# AD9959.net
KiCad netlist of a schematic drawn in Altium Designer
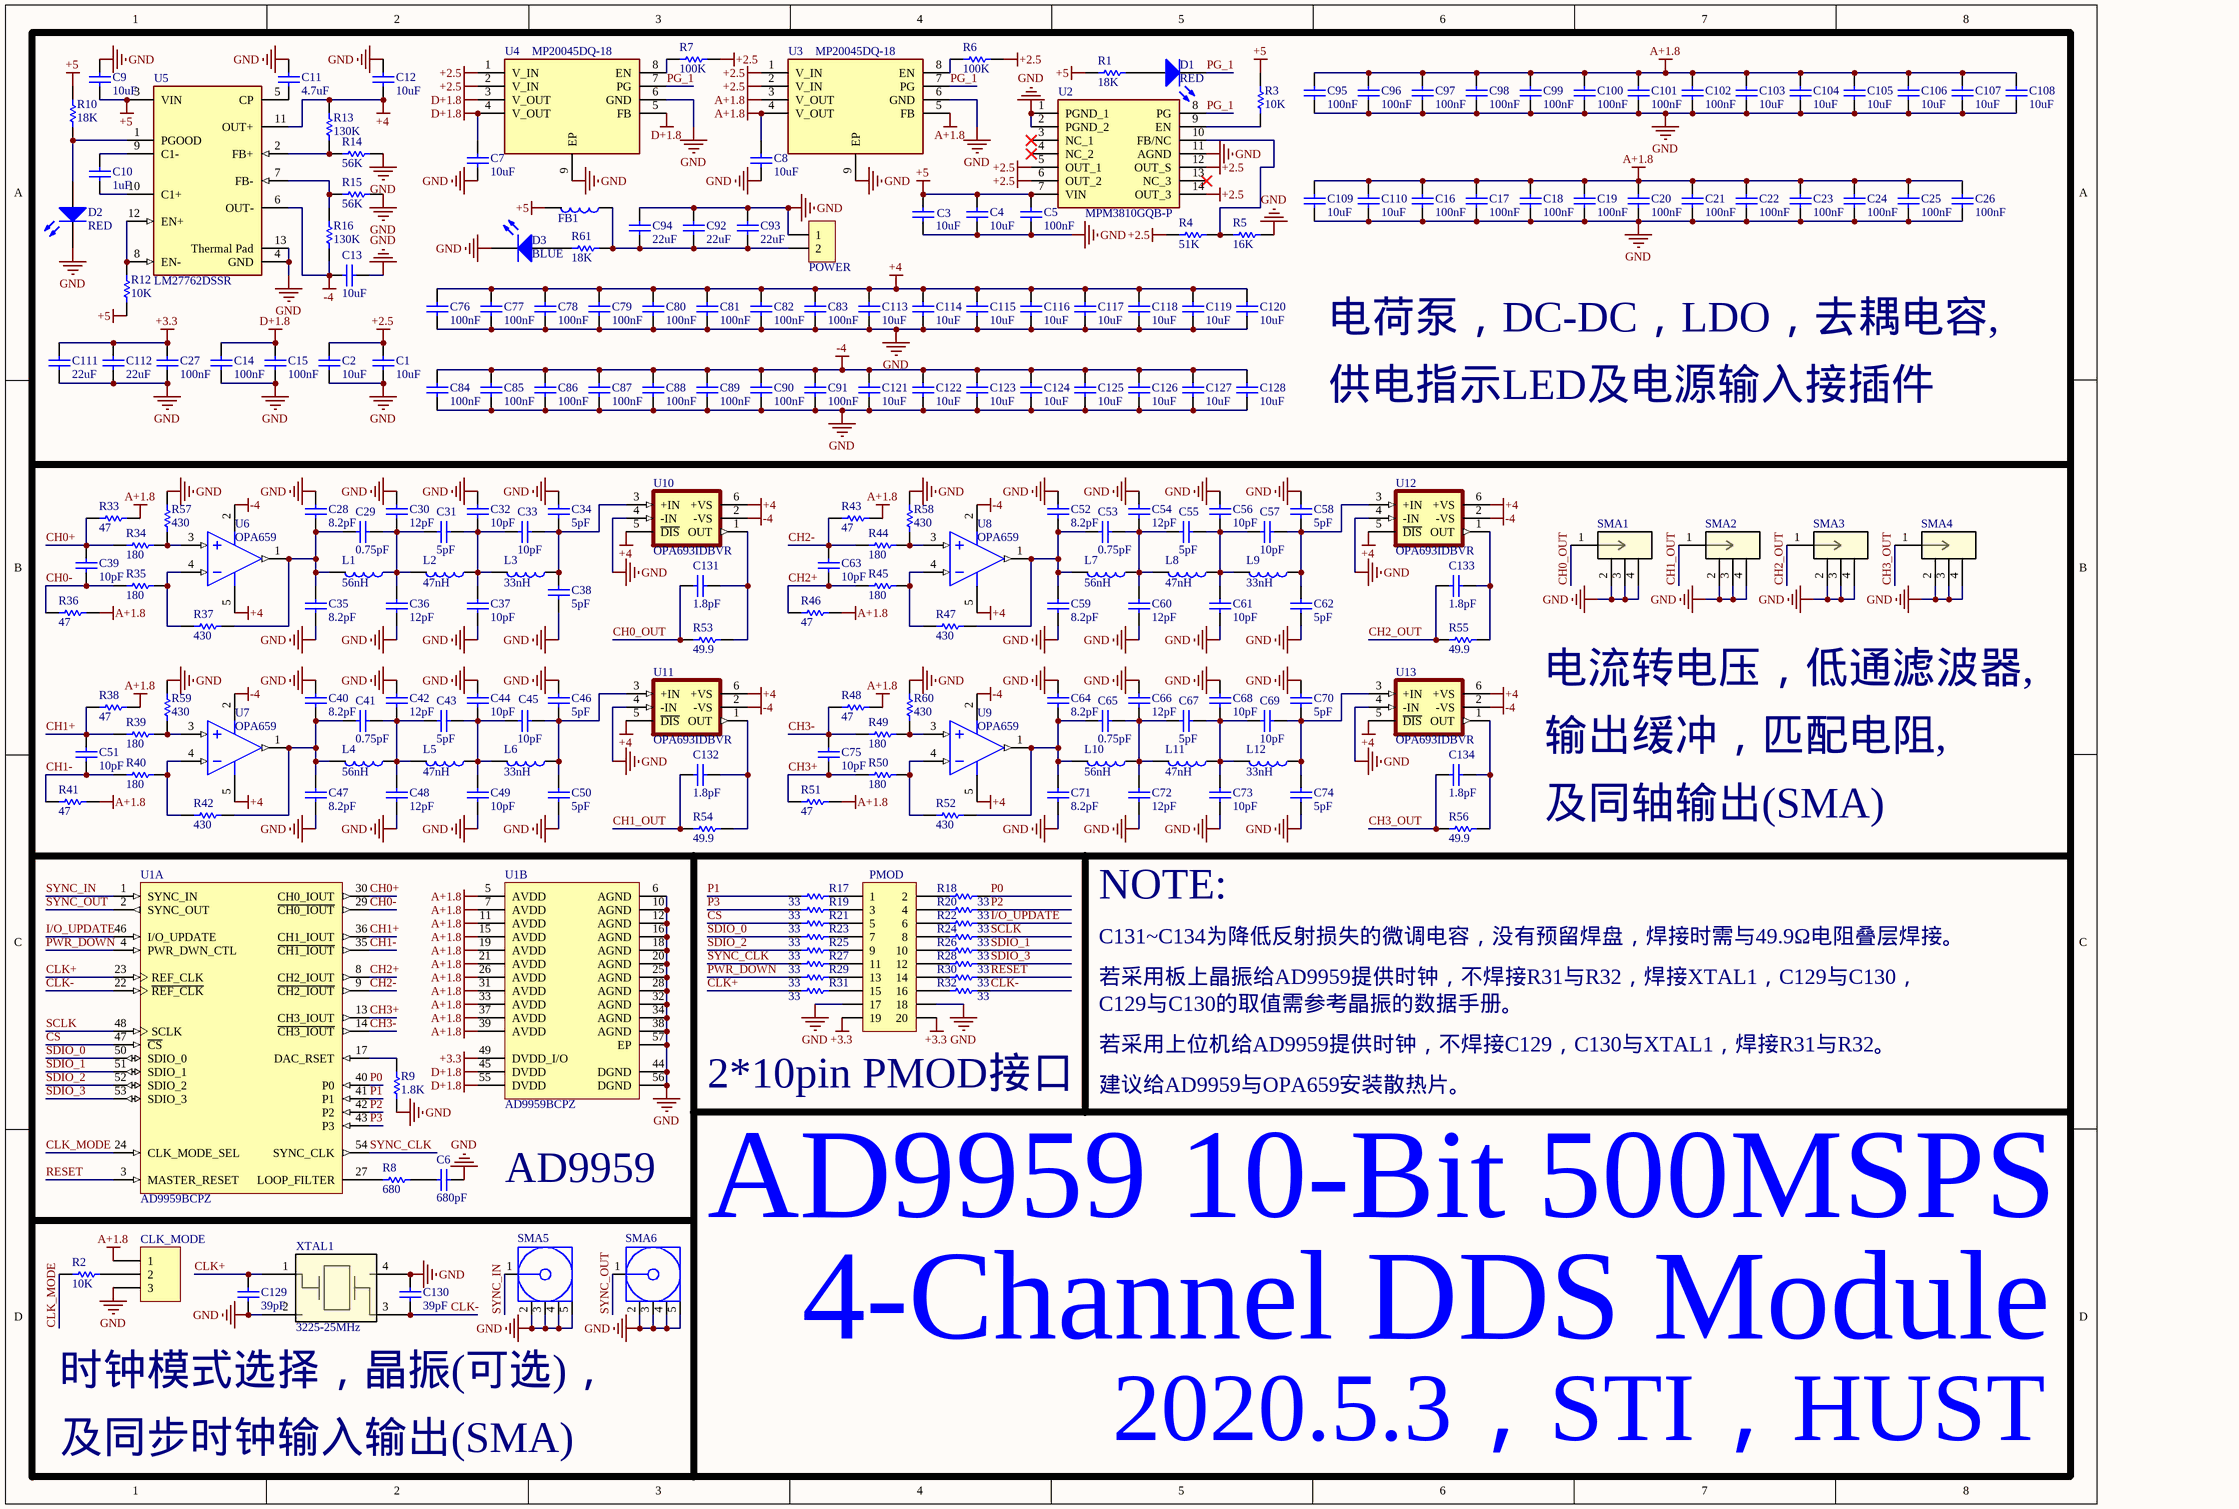
[diagram p0: AD9959.SchDoc]

(export (version "E")
  (design (tool "Eeschema 10.0.6"))
  (components
    (comp (ref "C1")
      (value "10uF")
      (footprint "1608[0603]")
      (description "Capacitor")
      (fields (field (name "PUBLISHER") "Altium Limited"))
      (libsource (lib "My Footprint") (part "CAP"))
    )
    (comp (ref "C2")
      (value "10uF")
      (footprint "1608[0603]")
      (description "Capacitor")
      (fields (field (name "PUBLISHER") "Altium Limited"))
      (libsource (lib "My Footprint") (part "CAP"))
    )
    (comp (ref "C3")
      (value "10uF")
      (footprint "1608[0603]")
      (description "Capacitor")
      (fields (field (name "PUBLISHER") "Altium Limited"))
      (libsource (lib "My Footprint") (part "CAP"))
    )
    (comp (ref "C4")
      (value "10uF")
      (footprint "1608[0603]")
      (description "Capacitor")
      (fields (field (name "PUBLISHER") "Altium Limited"))
      (libsource (lib "My Footprint") (part "CAP"))
    )
    (comp (ref "C5")
      (value "100nF")
      (footprint "0402")
      (description "Capacitor")
      (fields (field (name "PUBLISHER") "Altium Limited"))
      (libsource (lib "My Footprint") (part "CAP"))
    )
    (comp (ref "C6")
      (value "680pF")
      (footprint "0402")
      (description "Capacitor")
      (fields (field (name "PUBLISHER") "Altium Limited"))
      (libsource (lib "My Footprint") (part "CAP"))
    )
    (comp (ref "C7")
      (value "10uF")
      (footprint "1608[0603]")
      (description "Capacitor")
      (fields (field (name "PUBLISHER") "Altium Limited"))
      (libsource (lib "My Footprint") (part "CAP"))
    )
    (comp (ref "C8")
      (value "10uF")
      (footprint "1608[0603]")
      (description "Capacitor")
      (fields (field (name "PUBLISHER") "Altium Limited"))
      (libsource (lib "My Footprint") (part "CAP"))
    )
    (comp (ref "C9")
      (value "10uF")
      (footprint "1608[0603]")
      (description "Capacitor")
      (fields (field (name "PUBLISHER") "Altium Limited"))
      (libsource (lib "My Footprint") (part "CAP"))
    )
    (comp (ref "C10")
      (value "1uF")
      (footprint "0402")
      (description "Capacitor")
      (fields (field (name "PUBLISHER") "Altium Limited"))
      (libsource (lib "My Footprint") (part "CAP"))
    )
    (comp (ref "C11")
      (value "4.7uF")
      (footprint "1608[0603]")
      (description "Capacitor")
      (fields (field (name "PUBLISHER") "Altium Limited"))
      (libsource (lib "My Footprint") (part "CAP"))
    )
    (comp (ref "C12")
      (value "10uF")
      (footprint "1608[0603]")
      (description "Capacitor")
      (fields (field (name "PUBLISHER") "Altium Limited"))
      (libsource (lib "My Footprint") (part "CAP"))
    )
    (comp (ref "C13")
      (value "10uF")
      (footprint "1608[0603]")
      (description "Capacitor")
      (fields (field (name "PUBLISHER") "Altium Limited"))
      (libsource (lib "My Footprint") (part "CAP"))
    )
    (comp (ref "C14")
      (value "100nF")
      (footprint "0402")
      (description "Capacitor")
      (fields (field (name "PUBLISHER") "Altium Limited"))
      (libsource (lib "My Footprint") (part "CAP"))
    )
    (comp (ref "C15")
      (value "100nF")
      (footprint "0402")
      (description "Capacitor")
      (fields (field (name "PUBLISHER") "Altium Limited"))
      (libsource (lib "My Footprint") (part "CAP"))
    )
    (comp (ref "C16")
      (value "100nF")
      (footprint "0402")
      (description "Capacitor")
      (fields (field (name "PUBLISHER") "Altium Limited"))
      (libsource (lib "My Footprint") (part "CAP"))
    )
    (comp (ref "C17")
      (value "100nF")
      (footprint "0402")
      (description "Capacitor")
      (fields (field (name "PUBLISHER") "Altium Limited"))
      (libsource (lib "My Footprint") (part "CAP"))
    )
    (comp (ref "C18")
      (value "100nF")
      (footprint "0402")
      (description "Capacitor")
      (fields (field (name "PUBLISHER") "Altium Limited"))
      (libsource (lib "My Footprint") (part "CAP"))
    )
    (comp (ref "C19")
      (value "100nF")
      (footprint "0402")
      (description "Capacitor")
      (fields (field (name "PUBLISHER") "Altium Limited"))
      (libsource (lib "My Footprint") (part "CAP"))
    )
    (comp (ref "C20")
      (value "100nF")
      (footprint "0402")
      (description "Capacitor")
      (fields (field (name "PUBLISHER") "Altium Limited"))
      (libsource (lib "My Footprint") (part "CAP"))
    )
    (comp (ref "C21")
      (value "100nF")
      (footprint "0402")
      (description "Capacitor")
      (fields (field (name "PUBLISHER") "Altium Limited"))
      (libsource (lib "My Footprint") (part "CAP"))
    )
    (comp (ref "C22")
      (value "100nF")
      (footprint "0402")
      (description "Capacitor")
      (fields (field (name "PUBLISHER") "Altium Limited"))
      (libsource (lib "My Footprint") (part "CAP"))
    )
    (comp (ref "C23")
      (value "100nF")
      (footprint "0402")
      (description "Capacitor")
      (fields (field (name "PUBLISHER") "Altium Limited"))
      (libsource (lib "My Footprint") (part "CAP"))
    )
    (comp (ref "C24")
      (value "100nF")
      (footprint "0402")
      (description "Capacitor")
      (fields (field (name "PUBLISHER") "Altium Limited"))
      (libsource (lib "My Footprint") (part "CAP"))
    )
    (comp (ref "C25")
      (value "100nF")
      (footprint "0402")
      (description "Capacitor")
      (fields (field (name "PUBLISHER") "Altium Limited"))
      (libsource (lib "My Footprint") (part "CAP"))
    )
    (comp (ref "C26")
      (value "100nF")
      (footprint "0402")
      (description "Capacitor")
      (fields (field (name "PUBLISHER") "Altium Limited"))
      (libsource (lib "My Footprint") (part "CAP"))
    )
    (comp (ref "C27")
      (value "100nF")
      (footprint "0402")
      (description "Capacitor")
      (fields (field (name "PUBLISHER") "Altium Limited"))
      (libsource (lib "My Footprint") (part "CAP"))
    )
    (comp (ref "C28")
      (value "8.2pF")
      (footprint "0402")
      (description "Capacitor")
      (fields (field (name "PUBLISHER") "Altium Limited"))
      (libsource (lib "My Footprint") (part "CAP"))
    )
    (comp (ref "C29")
      (value "0.75pF")
      (footprint "0402")
      (description "Capacitor")
      (fields (field (name "PUBLISHER") "Altium Limited"))
      (libsource (lib "My Footprint") (part "CAP"))
    )
    (comp (ref "C30")
      (value "12pF")
      (footprint "0402")
      (description "Capacitor")
      (fields (field (name "PUBLISHER") "Altium Limited"))
      (libsource (lib "My Footprint") (part "CAP"))
    )
    (comp (ref "C31")
      (value "5pF")
      (footprint "0402")
      (description "Capacitor")
      (fields (field (name "PUBLISHER") "Altium Limited"))
      (libsource (lib "My Footprint") (part "CAP"))
    )
    (comp (ref "C32")
      (value "10pF")
      (footprint "0402")
      (description "Capacitor")
      (fields (field (name "PUBLISHER") "Altium Limited"))
      (libsource (lib "My Footprint") (part "CAP"))
    )
    (comp (ref "C33")
      (value "10pF")
      (footprint "0402")
      (description "Capacitor")
      (fields (field (name "PUBLISHER") "Altium Limited"))
      (libsource (lib "My Footprint") (part "CAP"))
    )
    (comp (ref "C34")
      (value "5pF")
      (footprint "0402")
      (description "Capacitor")
      (fields (field (name "PUBLISHER") "Altium Limited"))
      (libsource (lib "My Footprint") (part "CAP"))
    )
    (comp (ref "C35")
      (value "8.2pF")
      (footprint "0402")
      (description "Capacitor")
      (fields (field (name "PUBLISHER") "Altium Limited"))
      (libsource (lib "My Footprint") (part "CAP"))
    )
    (comp (ref "C36")
      (value "12pF")
      (footprint "0402")
      (description "Capacitor")
      (fields (field (name "PUBLISHER") "Altium Limited"))
      (libsource (lib "My Footprint") (part "CAP"))
    )
    (comp (ref "C37")
      (value "10pF")
      (footprint "0402")
      (description "Capacitor")
      (fields (field (name "PUBLISHER") "Altium Limited"))
      (libsource (lib "My Footprint") (part "CAP"))
    )
    (comp (ref "C38")
      (value "5pF")
      (footprint "0402")
      (description "Capacitor")
      (fields (field (name "PUBLISHER") "Altium Limited"))
      (libsource (lib "My Footprint") (part "CAP"))
    )
    (comp (ref "C39")
      (value "10pF")
      (footprint "0402")
      (description "Capacitor")
      (fields (field (name "PUBLISHER") "Altium Limited"))
      (libsource (lib "My Footprint") (part "CAP"))
    )
    (comp (ref "C40")
      (value "8.2pF")
      (footprint "0402")
      (description "Capacitor")
      (fields (field (name "PUBLISHER") "Altium Limited"))
      (libsource (lib "My Footprint") (part "CAP"))
    )
    (comp (ref "C41")
      (value "0.75pF")
      (footprint "0402")
      (description "Capacitor")
      (fields (field (name "PUBLISHER") "Altium Limited"))
      (libsource (lib "My Footprint") (part "CAP"))
    )
    (comp (ref "C42")
      (value "12pF")
      (footprint "0402")
      (description "Capacitor")
      (fields (field (name "PUBLISHER") "Altium Limited"))
      (libsource (lib "My Footprint") (part "CAP"))
    )
    (comp (ref "C43")
      (value "5pF")
      (footprint "0402")
      (description "Capacitor")
      (fields (field (name "PUBLISHER") "Altium Limited"))
      (libsource (lib "My Footprint") (part "CAP"))
    )
    (comp (ref "C44")
      (value "10pF")
      (footprint "0402")
      (description "Capacitor")
      (fields (field (name "PUBLISHER") "Altium Limited"))
      (libsource (lib "My Footprint") (part "CAP"))
    )
    (comp (ref "C45")
      (value "10pF")
      (footprint "0402")
      (description "Capacitor")
      (fields (field (name "PUBLISHER") "Altium Limited"))
      (libsource (lib "My Footprint") (part "CAP"))
    )
    (comp (ref "C46")
      (value "5pF")
      (footprint "0402")
      (description "Capacitor")
      (fields (field (name "PUBLISHER") "Altium Limited"))
      (libsource (lib "My Footprint") (part "CAP"))
    )
    (comp (ref "C47")
      (value "8.2pF")
      (footprint "0402")
      (description "Capacitor")
      (fields (field (name "PUBLISHER") "Altium Limited"))
      (libsource (lib "My Footprint") (part "CAP"))
    )
    (comp (ref "C48")
      (value "12pF")
      (footprint "0402")
      (description "Capacitor")
      (fields (field (name "PUBLISHER") "Altium Limited"))
      (libsource (lib "My Footprint") (part "CAP"))
    )
    (comp (ref "C49")
      (value "10pF")
      (footprint "0402")
      (description "Capacitor")
      (fields (field (name "PUBLISHER") "Altium Limited"))
      (libsource (lib "My Footprint") (part "CAP"))
    )
    (comp (ref "C50")
      (value "5pF")
      (footprint "0402")
      (description "Capacitor")
      (fields (field (name "PUBLISHER") "Altium Limited"))
      (libsource (lib "My Footprint") (part "CAP"))
    )
    (comp (ref "C51")
      (value "10pF")
      (footprint "0402")
      (description "Capacitor")
      (fields (field (name "PUBLISHER") "Altium Limited"))
      (libsource (lib "My Footprint") (part "CAP"))
    )
    (comp (ref "C52")
      (value "8.2pF")
      (footprint "0402")
      (description "Capacitor")
      (fields (field (name "PUBLISHER") "Altium Limited"))
      (libsource (lib "My Footprint") (part "CAP"))
    )
    (comp (ref "C53")
      (value "0.75pF")
      (footprint "0402")
      (description "Capacitor")
      (fields (field (name "PUBLISHER") "Altium Limited"))
      (libsource (lib "My Footprint") (part "CAP"))
    )
    (comp (ref "C54")
      (value "12pF")
      (footprint "0402")
      (description "Capacitor")
      (fields (field (name "PUBLISHER") "Altium Limited"))
      (libsource (lib "My Footprint") (part "CAP"))
    )
    (comp (ref "C55")
      (value "5pF")
      (footprint "0402")
      (description "Capacitor")
      (fields (field (name "PUBLISHER") "Altium Limited"))
      (libsource (lib "My Footprint") (part "CAP"))
    )
    (comp (ref "C56")
      (value "10pF")
      (footprint "0402")
      (description "Capacitor")
      (fields (field (name "PUBLISHER") "Altium Limited"))
      (libsource (lib "My Footprint") (part "CAP"))
    )
    (comp (ref "C57")
      (value "10pF")
      (footprint "0402")
      (description "Capacitor")
      (fields (field (name "PUBLISHER") "Altium Limited"))
      (libsource (lib "My Footprint") (part "CAP"))
    )
    (comp (ref "C58")
      (value "5pF")
      (footprint "0402")
      (description "Capacitor")
      (fields (field (name "PUBLISHER") "Altium Limited"))
      (libsource (lib "My Footprint") (part "CAP"))
    )
    (comp (ref "C59")
      (value "8.2pF")
      (footprint "0402")
      (description "Capacitor")
      (fields (field (name "PUBLISHER") "Altium Limited"))
      (libsource (lib "My Footprint") (part "CAP"))
    )
    (comp (ref "C60")
      (value "12pF")
      (footprint "0402")
      (description "Capacitor")
      (fields (field (name "PUBLISHER") "Altium Limited"))
      (libsource (lib "My Footprint") (part "CAP"))
    )
    (comp (ref "C61")
      (value "10pF")
      (footprint "0402")
      (description "Capacitor")
      (fields (field (name "PUBLISHER") "Altium Limited"))
      (libsource (lib "My Footprint") (part "CAP"))
    )
    (comp (ref "C62")
      (value "5pF")
      (footprint "0402")
      (description "Capacitor")
      (fields (field (name "PUBLISHER") "Altium Limited"))
      (libsource (lib "My Footprint") (part "CAP"))
    )
    (comp (ref "C63")
      (value "10pF")
      (footprint "0402")
      (description "Capacitor")
      (fields (field (name "PUBLISHER") "Altium Limited"))
      (libsource (lib "My Footprint") (part "CAP"))
    )
    (comp (ref "C64")
      (value "8.2pF")
      (footprint "0402")
      (description "Capacitor")
      (fields (field (name "PUBLISHER") "Altium Limited"))
      (libsource (lib "My Footprint") (part "CAP"))
    )
    (comp (ref "C65")
      (value "0.75pF")
      (footprint "0402")
      (description "Capacitor")
      (fields (field (name "PUBLISHER") "Altium Limited"))
      (libsource (lib "My Footprint") (part "CAP"))
    )
    (comp (ref "C66")
      (value "12pF")
      (footprint "0402")
      (description "Capacitor")
      (fields (field (name "PUBLISHER") "Altium Limited"))
      (libsource (lib "My Footprint") (part "CAP"))
    )
    (comp (ref "C67")
      (value "5pF")
      (footprint "0402")
      (description "Capacitor")
      (fields (field (name "PUBLISHER") "Altium Limited"))
      (libsource (lib "My Footprint") (part "CAP"))
    )
    (comp (ref "C68")
      (value "10pF")
      (footprint "0402")
      (description "Capacitor")
      (fields (field (name "PUBLISHER") "Altium Limited"))
      (libsource (lib "My Footprint") (part "CAP"))
    )
    (comp (ref "C69")
      (value "10pF")
      (footprint "0402")
      (description "Capacitor")
      (fields (field (name "PUBLISHER") "Altium Limited"))
      (libsource (lib "My Footprint") (part "CAP"))
    )
    (comp (ref "C70")
      (value "5pF")
      (footprint "0402")
      (description "Capacitor")
      (fields (field (name "PUBLISHER") "Altium Limited"))
      (libsource (lib "My Footprint") (part "CAP"))
    )
    (comp (ref "C71")
      (value "8.2pF")
      (footprint "0402")
      (description "Capacitor")
      (fields (field (name "PUBLISHER") "Altium Limited"))
      (libsource (lib "My Footprint") (part "CAP"))
    )
    (comp (ref "C72")
      (value "12pF")
      (footprint "0402")
      (description "Capacitor")
      (fields (field (name "PUBLISHER") "Altium Limited"))
      (libsource (lib "My Footprint") (part "CAP"))
    )
    (comp (ref "C73")
      (value "10pF")
      (footprint "0402")
      (description "Capacitor")
      (fields (field (name "PUBLISHER") "Altium Limited"))
      (libsource (lib "My Footprint") (part "CAP"))
    )
    (comp (ref "C74")
      (value "5pF")
      (footprint "0402")
      (description "Capacitor")
      (fields (field (name "PUBLISHER") "Altium Limited"))
      (libsource (lib "My Footprint") (part "CAP"))
    )
    (comp (ref "C75")
      (value "10pF")
      (footprint "0402")
      (description "Capacitor")
      (fields (field (name "PUBLISHER") "Altium Limited"))
      (libsource (lib "My Footprint") (part "CAP"))
    )
    (comp (ref "C76")
      (value "100nF")
      (footprint "0402")
      (description "Capacitor")
      (fields (field (name "PUBLISHER") "Altium Limited"))
      (libsource (lib "My Footprint") (part "CAP"))
    )
    (comp (ref "C77")
      (value "100nF")
      (footprint "0402")
      (description "Capacitor")
      (fields (field (name "PUBLISHER") "Altium Limited"))
      (libsource (lib "My Footprint") (part "CAP"))
    )
    (comp (ref "C78")
      (value "100nF")
      (footprint "0402")
      (description "Capacitor")
      (fields (field (name "PUBLISHER") "Altium Limited"))
      (libsource (lib "My Footprint") (part "CAP"))
    )
    (comp (ref "C79")
      (value "100nF")
      (footprint "0402")
      (description "Capacitor")
      (fields (field (name "PUBLISHER") "Altium Limited"))
      (libsource (lib "My Footprint") (part "CAP"))
    )
    (comp (ref "C80")
      (value "100nF")
      (footprint "0402")
      (description "Capacitor")
      (fields (field (name "PUBLISHER") "Altium Limited"))
      (libsource (lib "My Footprint") (part "CAP"))
    )
    (comp (ref "C81")
      (value "100nF")
      (footprint "0402")
      (description "Capacitor")
      (fields (field (name "PUBLISHER") "Altium Limited"))
      (libsource (lib "My Footprint") (part "CAP"))
    )
    (comp (ref "C82")
      (value "100nF")
      (footprint "0402")
      (description "Capacitor")
      (fields (field (name "PUBLISHER") "Altium Limited"))
      (libsource (lib "My Footprint") (part "CAP"))
    )
    (comp (ref "C83")
      (value "100nF")
      (footprint "0402")
      (description "Capacitor")
      (fields (field (name "PUBLISHER") "Altium Limited"))
      (libsource (lib "My Footprint") (part "CAP"))
    )
    (comp (ref "C84")
      (value "100nF")
      (footprint "0402")
      (description "Capacitor")
      (fields (field (name "PUBLISHER") "Altium Limited"))
      (libsource (lib "My Footprint") (part "CAP"))
    )
    (comp (ref "C85")
      (value "100nF")
      (footprint "0402")
      (description "Capacitor")
      (fields (field (name "PUBLISHER") "Altium Limited"))
      (libsource (lib "My Footprint") (part "CAP"))
    )
    (comp (ref "C86")
      (value "100nF")
      (footprint "0402")
      (description "Capacitor")
      (fields (field (name "PUBLISHER") "Altium Limited"))
      (libsource (lib "My Footprint") (part "CAP"))
    )
    (comp (ref "C87")
      (value "100nF")
      (footprint "0402")
      (description "Capacitor")
      (fields (field (name "PUBLISHER") "Altium Limited"))
      (libsource (lib "My Footprint") (part "CAP"))
    )
    (comp (ref "C88")
      (value "100nF")
      (footprint "0402")
      (description "Capacitor")
      (fields (field (name "PUBLISHER") "Altium Limited"))
      (libsource (lib "My Footprint") (part "CAP"))
    )
    (comp (ref "C89")
      (value "100nF")
      (footprint "0402")
      (description "Capacitor")
      (fields (field (name "PUBLISHER") "Altium Limited"))
      (libsource (lib "My Footprint") (part "CAP"))
    )
    (comp (ref "C90")
      (value "100nF")
      (footprint "0402")
      (description "Capacitor")
      (fields (field (name "PUBLISHER") "Altium Limited"))
      (libsource (lib "My Footprint") (part "CAP"))
    )
    (comp (ref "C91")
      (value "100nF")
      (footprint "0402")
      (description "Capacitor")
      (fields (field (name "PUBLISHER") "Altium Limited"))
      (libsource (lib "My Footprint") (part "CAP"))
    )
    (comp (ref "C92")
      (value "22uF")
      (footprint "6-0805_L")
      (description "Capacitor")
      (fields (field (name "PUBLISHER") "Altium Limited"))
      (libsource (lib "My Footprint") (part "CAP"))
    )
    (comp (ref "C93")
      (value "22uF")
      (footprint "6-0805_L")
      (description "Capacitor")
      (fields (field (name "PUBLISHER") "Altium Limited"))
      (libsource (lib "My Footprint") (part "CAP"))
    )
    (comp (ref "C94")
      (value "22uF")
      (footprint "6-0805_L")
      (description "Capacitor")
      (fields (field (name "PUBLISHER") "Altium Limited"))
      (libsource (lib "My Footprint") (part "CAP"))
    )
    (comp (ref "C95")
      (value "100nF")
      (footprint "0402")
      (description "Capacitor")
      (fields (field (name "PUBLISHER") "Altium Limited"))
      (libsource (lib "My Footprint") (part "CAP"))
    )
    (comp (ref "C96")
      (value "100nF")
      (footprint "0402")
      (description "Capacitor")
      (fields (field (name "PUBLISHER") "Altium Limited"))
      (libsource (lib "My Footprint") (part "CAP"))
    )
    (comp (ref "C97")
      (value "100nF")
      (footprint "0402")
      (description "Capacitor")
      (fields (field (name "PUBLISHER") "Altium Limited"))
      (libsource (lib "My Footprint") (part "CAP"))
    )
    (comp (ref "C98")
      (value "100nF")
      (footprint "0402")
      (description "Capacitor")
      (fields (field (name "PUBLISHER") "Altium Limited"))
      (libsource (lib "My Footprint") (part "CAP"))
    )
    (comp (ref "C99")
      (value "100nF")
      (footprint "0402")
      (description "Capacitor")
      (fields (field (name "PUBLISHER") "Altium Limited"))
      (libsource (lib "My Footprint") (part "CAP"))
    )
    (comp (ref "C100")
      (value "100nF")
      (footprint "0402")
      (description "Capacitor")
      (fields (field (name "PUBLISHER") "Altium Limited"))
      (libsource (lib "My Footprint") (part "CAP"))
    )
    (comp (ref "C101")
      (value "100nF")
      (footprint "0402")
      (description "Capacitor")
      (fields (field (name "PUBLISHER") "Altium Limited"))
      (libsource (lib "My Footprint") (part "CAP"))
    )
    (comp (ref "C102")
      (value "100nF")
      (footprint "0402")
      (description "Capacitor")
      (fields (field (name "PUBLISHER") "Altium Limited"))
      (libsource (lib "My Footprint") (part "CAP"))
    )
    (comp (ref "C103")
      (value "10uF")
      (footprint "0402")
      (description "Capacitor")
      (fields (field (name "PUBLISHER") "Altium Limited"))
      (libsource (lib "My Footprint") (part "CAP"))
    )
    (comp (ref "C104")
      (value "10uF")
      (footprint "0402")
      (description "Capacitor")
      (fields (field (name "PUBLISHER") "Altium Limited"))
      (libsource (lib "My Footprint") (part "CAP"))
    )
    (comp (ref "C105")
      (value "10uF")
      (footprint "0402")
      (description "Capacitor")
      (fields (field (name "PUBLISHER") "Altium Limited"))
      (libsource (lib "My Footprint") (part "CAP"))
    )
    (comp (ref "C106")
      (value "10uF")
      (footprint "0402")
      (description "Capacitor")
      (fields (field (name "PUBLISHER") "Altium Limited"))
      (libsource (lib "My Footprint") (part "CAP"))
    )
    (comp (ref "C107")
      (value "10uF")
      (footprint "0402")
      (description "Capacitor")
      (fields (field (name "PUBLISHER") "Altium Limited"))
      (libsource (lib "My Footprint") (part "CAP"))
    )
    (comp (ref "C108")
      (value "10uF")
      (footprint "0402")
      (description "Capacitor")
      (fields (field (name "PUBLISHER") "Altium Limited"))
      (libsource (lib "My Footprint") (part "CAP"))
    )
    (comp (ref "C109")
      (value "10uF")
      (footprint "0402")
      (description "Capacitor")
      (fields (field (name "PUBLISHER") "Altium Limited"))
      (libsource (lib "My Footprint") (part "CAP"))
    )
    (comp (ref "C110")
      (value "10uF")
      (footprint "0402")
      (description "Capacitor")
      (fields (field (name "PUBLISHER") "Altium Limited"))
      (libsource (lib "My Footprint") (part "CAP"))
    )
    (comp (ref "C111")
      (value "22uF")
      (footprint "6-0805_L")
      (description "Capacitor")
      (fields (field (name "PUBLISHER") "Altium Limited"))
      (libsource (lib "My Footprint") (part "CAP"))
    )
    (comp (ref "C112")
      (value "22uF")
      (footprint "6-0805_L")
      (description "Capacitor")
      (fields (field (name "PUBLISHER") "Altium Limited"))
      (libsource (lib "My Footprint") (part "CAP"))
    )
    (comp (ref "C113")
      (value "10uF")
      (footprint "0402")
      (description "Capacitor")
      (fields (field (name "PUBLISHER") "Altium Limited"))
      (libsource (lib "My Footprint") (part "CAP"))
    )
    (comp (ref "C114")
      (value "10uF")
      (footprint "0402")
      (description "Capacitor")
      (fields (field (name "PUBLISHER") "Altium Limited"))
      (libsource (lib "My Footprint") (part "CAP"))
    )
    (comp (ref "C115")
      (value "10uF")
      (footprint "0402")
      (description "Capacitor")
      (fields (field (name "PUBLISHER") "Altium Limited"))
      (libsource (lib "My Footprint") (part "CAP"))
    )
    (comp (ref "C116")
      (value "10uF")
      (footprint "0402")
      (description "Capacitor")
      (fields (field (name "PUBLISHER") "Altium Limited"))
      (libsource (lib "My Footprint") (part "CAP"))
    )
    (comp (ref "C117")
      (value "10uF")
      (footprint "0402")
      (description "Capacitor")
      (fields (field (name "PUBLISHER") "Altium Limited"))
      (libsource (lib "My Footprint") (part "CAP"))
    )
    (comp (ref "C118")
      (value "10uF")
      (footprint "0402")
      (description "Capacitor")
      (fields (field (name "PUBLISHER") "Altium Limited"))
      (libsource (lib "My Footprint") (part "CAP"))
    )
    (comp (ref "C119")
      (value "10uF")
      (footprint "0402")
      (description "Capacitor")
      (fields (field (name "PUBLISHER") "Altium Limited"))
      (libsource (lib "My Footprint") (part "CAP"))
    )
    (comp (ref "C120")
      (value "10uF")
      (footprint "0402")
      (description "Capacitor")
      (fields (field (name "PUBLISHER") "Altium Limited"))
      (libsource (lib "My Footprint") (part "CAP"))
    )
    (comp (ref "C121")
      (value "10uF")
      (footprint "0402")
      (description "Capacitor")
      (fields (field (name "PUBLISHER") "Altium Limited"))
      (libsource (lib "My Footprint") (part "CAP"))
    )
    (comp (ref "C122")
      (value "10uF")
      (footprint "0402")
      (description "Capacitor")
      (fields (field (name "PUBLISHER") "Altium Limited"))
      (libsource (lib "My Footprint") (part "CAP"))
    )
    (comp (ref "C123")
      (value "10uF")
      (footprint "0402")
      (description "Capacitor")
      (fields (field (name "PUBLISHER") "Altium Limited"))
      (libsource (lib "My Footprint") (part "CAP"))
    )
    (comp (ref "C124")
      (value "10uF")
      (footprint "0402")
      (description "Capacitor")
      (fields (field (name "PUBLISHER") "Altium Limited"))
      (libsource (lib "My Footprint") (part "CAP"))
    )
    (comp (ref "C125")
      (value "10uF")
      (footprint "0402")
      (description "Capacitor")
      (fields (field (name "PUBLISHER") "Altium Limited"))
      (libsource (lib "My Footprint") (part "CAP"))
    )
    (comp (ref "C126")
      (value "10uF")
      (footprint "0402")
      (description "Capacitor")
      (fields (field (name "PUBLISHER") "Altium Limited"))
      (libsource (lib "My Footprint") (part "CAP"))
    )
    (comp (ref "C127")
      (value "10uF")
      (footprint "0402")
      (description "Capacitor")
      (fields (field (name "PUBLISHER") "Altium Limited"))
      (libsource (lib "My Footprint") (part "CAP"))
    )
    (comp (ref "C128")
      (value "10uF")
      (footprint "0402")
      (description "Capacitor")
      (fields (field (name "PUBLISHER") "Altium Limited"))
      (libsource (lib "My Footprint") (part "CAP"))
    )
    (comp (ref "C129")
      (value "39pF")
      (footprint "0402")
      (description "Capacitor")
      (fields (field (name "PUBLISHER") "Altium Limited"))
      (libsource (lib "My Footprint") (part "CAP"))
    )
    (comp (ref "C130")
      (value "39pF")
      (footprint "0402")
      (description "Capacitor")
      (fields (field (name "PUBLISHER") "Altium Limited"))
      (libsource (lib "My Footprint") (part "CAP"))
    )
    (comp (ref "C131")
      (value "1.8pF")
      (footprint "0402")
      (description "Capacitor")
      (fields (field (name "PUBLISHER") "Altium Limited"))
      (libsource (lib "My Footprint") (part "CAP"))
    )
    (comp (ref "C132")
      (value "1.8pF")
      (footprint "0402")
      (description "Capacitor")
      (fields (field (name "PUBLISHER") "Altium Limited"))
      (libsource (lib "My Footprint") (part "CAP"))
    )
    (comp (ref "C133")
      (value "1.8pF")
      (footprint "0402")
      (description "Capacitor")
      (fields (field (name "PUBLISHER") "Altium Limited"))
      (libsource (lib "My Footprint") (part "CAP"))
    )
    (comp (ref "C134")
      (value "1.8pF")
      (footprint "0402")
      (description "Capacitor")
      (fields (field (name "PUBLISHER") "Altium Limited"))
      (libsource (lib "My Footprint") (part "CAP"))
    )
    (comp (ref "CLK_MODE")
      (value "Header 3")
      (footprint "HDR1X3")
      (description "Header, 3-Pin")
      (fields (field (name "PUBLISHER") "Altium Limited"))
      (libsource (lib "Miscellaneous Connectors") (part "Header 3"))
    )
    (comp (ref "D1")
      (value "RED")
      (footprint "1608[0603]")
      (description "Typical INFRARED GaAs LED")
      (fields (field (name "PUBLISHER") "Altium Limited"))
      (libsource (lib "Miscellaneous Devices") (part "LED0"))
    )
    (comp (ref "D2")
      (value "RED")
      (footprint "1608[0603]")
      (description "Typical INFRARED GaAs LED")
      (fields (field (name "PUBLISHER") "Altium Limited"))
      (libsource (lib "Miscellaneous Devices") (part "LED0"))
    )
    (comp (ref "D3")
      (value "BLUE")
      (footprint "1608[0603]")
      (description "Typical INFRARED GaAs LED")
      (fields (field (name "PUBLISHER") "Altium Limited"))
      (libsource (lib "Miscellaneous Devices") (part "LED0"))
    )
    (comp (ref "FB1")
      (value "100R,100MHz, 0603")
      (footprint "1608[0603]")
      (description "磁珠")
      (libsource (lib "My Footprint") (part "FB"))
    )
    (comp (ref "L1")
      (value "56nH")
      (footprint "0402")
      (description "磁珠")
      (libsource (lib "My Footprint") (part "FB"))
    )
    (comp (ref "L2")
      (value "47nH")
      (footprint "0402")
      (description "磁珠")
      (libsource (lib "My Footprint") (part "FB"))
    )
    (comp (ref "L3")
      (value "33nH")
      (footprint "0402")
      (description "磁珠")
      (libsource (lib "My Footprint") (part "FB"))
    )
    (comp (ref "L4")
      (value "56nH")
      (footprint "0402")
      (description "磁珠")
      (libsource (lib "My Footprint") (part "FB"))
    )
    (comp (ref "L5")
      (value "47nH")
      (footprint "0402")
      (description "磁珠")
      (libsource (lib "My Footprint") (part "FB"))
    )
    (comp (ref "L6")
      (value "33nH")
      (footprint "0402")
      (description "磁珠")
      (libsource (lib "My Footprint") (part "FB"))
    )
    (comp (ref "L7")
      (value "56nH")
      (footprint "0402")
      (description "磁珠")
      (libsource (lib "My Footprint") (part "FB"))
    )
    (comp (ref "L8")
      (value "47nH")
      (footprint "0402")
      (description "磁珠")
      (libsource (lib "My Footprint") (part "FB"))
    )
    (comp (ref "L9")
      (value "33nH")
      (footprint "0402")
      (description "磁珠")
      (libsource (lib "My Footprint") (part "FB"))
    )
    (comp (ref "L10")
      (value "56nH")
      (footprint "0402")
      (description "磁珠")
      (libsource (lib "My Footprint") (part "FB"))
    )
    (comp (ref "L11")
      (value "47nH")
      (footprint "0402")
      (description "磁珠")
      (libsource (lib "My Footprint") (part "FB"))
    )
    (comp (ref "L12")
      (value "33nH")
      (footprint "0402")
      (description "磁珠")
      (libsource (lib "My Footprint") (part "FB"))
    )
    (comp (ref "PMOD")
      (value "Header 2X10")
      (footprint "201R2X10")
      (description "10*2P接插件")
      (libsource (lib "2x10_PMOD") (part "Header 10X2"))
    )
    (comp (ref "POWER")
      (value "HDR-1X2")
      (footprint "KF2510-LI-2P")
      (description "2P接插件")
      (libsource (lib "2510_2P") (part "Header 2"))
    )
    (comp (ref "R1")
      (value "18K")
      (footprint "0402")
      (description "Resistor")
      (fields (field (name "PUBLISHER") "Altium Limited"))
      (libsource (lib "My Footprint") (part "RES"))
    )
    (comp (ref "R2")
      (value "10K")
      (footprint "0402")
      (description "Resistor")
      (fields (field (name "PUBLISHER") "Altium Limited"))
      (libsource (lib "My Footprint") (part "RES"))
    )
    (comp (ref "R3")
      (value "10K")
      (footprint "0402")
      (description "Resistor")
      (fields (field (name "PUBLISHER") "Altium Limited"))
      (libsource (lib "My Footprint") (part "RES"))
    )
    (comp (ref "R4")
      (value "51K")
      (footprint "0402")
      (description "Resistor")
      (fields (field (name "PUBLISHER") "Altium Limited"))
      (libsource (lib "My Footprint") (part "RES"))
    )
    (comp (ref "R5")
      (value "16K")
      (footprint "0402")
      (description "Resistor")
      (fields (field (name "PUBLISHER") "Altium Limited"))
      (libsource (lib "My Footprint") (part "RES"))
    )
    (comp (ref "R6")
      (value "100K")
      (footprint "0402")
      (description "Resistor")
      (fields (field (name "PUBLISHER") "Altium Limited"))
      (libsource (lib "My Footprint") (part "RES"))
    )
    (comp (ref "R7")
      (value "100K")
      (footprint "0402")
      (description "Resistor")
      (fields (field (name "PUBLISHER") "Altium Limited"))
      (libsource (lib "My Footprint") (part "RES"))
    )
    (comp (ref "R8")
      (value "680")
      (footprint "0402")
      (description "Resistor")
      (fields (field (name "PUBLISHER") "Altium Limited"))
      (libsource (lib "My Footprint") (part "RES"))
    )
    (comp (ref "R9")
      (value "1.8K")
      (footprint "0402")
      (description "Resistor")
      (fields (field (name "PUBLISHER") "Altium Limited"))
      (libsource (lib "My Footprint") (part "RES"))
    )
    (comp (ref "R10")
      (value "18K")
      (footprint "0402")
      (description "Resistor")
      (fields (field (name "PUBLISHER") "Altium Limited"))
      (libsource (lib "My Footprint") (part "RES"))
    )
    (comp (ref "R12")
      (value "10K")
      (footprint "0402")
      (description "Resistor")
      (fields (field (name "PUBLISHER") "Altium Limited"))
      (libsource (lib "My Footprint") (part "RES"))
    )
    (comp (ref "R13")
      (value "130K")
      (footprint "0402")
      (description "Resistor")
      (fields (field (name "PUBLISHER") "Altium Limited"))
      (libsource (lib "My Footprint") (part "RES"))
    )
    (comp (ref "R14")
      (value "56K")
      (footprint "0402")
      (description "Resistor")
      (fields (field (name "PUBLISHER") "Altium Limited"))
      (libsource (lib "My Footprint") (part "RES"))
    )
    (comp (ref "R15")
      (value "56K")
      (footprint "0402")
      (description "Resistor")
      (fields (field (name "PUBLISHER") "Altium Limited"))
      (libsource (lib "My Footprint") (part "RES"))
    )
    (comp (ref "R16")
      (value "130K")
      (footprint "0402")
      (description "Resistor")
      (fields (field (name "PUBLISHER") "Altium Limited"))
      (libsource (lib "My Footprint") (part "RES"))
    )
    (comp (ref "R17")
      (value "33")
      (footprint "0402")
      (description "Resistor")
      (fields (field (name "PUBLISHER") "Altium Limited"))
      (libsource (lib "My Footprint") (part "RES"))
    )
    (comp (ref "R18")
      (value "33")
      (footprint "0402")
      (description "Resistor")
      (fields (field (name "PUBLISHER") "Altium Limited"))
      (libsource (lib "My Footprint") (part "RES"))
    )
    (comp (ref "R19")
      (value "33")
      (footprint "0402")
      (description "Resistor")
      (fields (field (name "PUBLISHER") "Altium Limited"))
      (libsource (lib "My Footprint") (part "RES"))
    )
    (comp (ref "R20")
      (value "33")
      (footprint "0402")
      (description "Resistor")
      (fields (field (name "PUBLISHER") "Altium Limited"))
      (libsource (lib "My Footprint") (part "RES"))
    )
    (comp (ref "R21")
      (value "33")
      (footprint "0402")
      (description "Resistor")
      (fields (field (name "PUBLISHER") "Altium Limited"))
      (libsource (lib "My Footprint") (part "RES"))
    )
    (comp (ref "R22")
      (value "33")
      (footprint "0402")
      (description "Resistor")
      (fields (field (name "PUBLISHER") "Altium Limited"))
      (libsource (lib "My Footprint") (part "RES"))
    )
    (comp (ref "R23")
      (value "33")
      (footprint "0402")
      (description "Resistor")
      (fields (field (name "PUBLISHER") "Altium Limited"))
      (libsource (lib "My Footprint") (part "RES"))
    )
    (comp (ref "R24")
      (value "33")
      (footprint "0402")
      (description "Resistor")
      (fields (field (name "PUBLISHER") "Altium Limited"))
      (libsource (lib "My Footprint") (part "RES"))
    )
    (comp (ref "R25")
      (value "33")
      (footprint "0402")
      (description "Resistor")
      (fields (field (name "PUBLISHER") "Altium Limited"))
      (libsource (lib "My Footprint") (part "RES"))
    )
    (comp (ref "R26")
      (value "33")
      (footprint "0402")
      (description "Resistor")
      (fields (field (name "PUBLISHER") "Altium Limited"))
      (libsource (lib "My Footprint") (part "RES"))
    )
    (comp (ref "R27")
      (value "33")
      (footprint "0402")
      (description "Resistor")
      (fields (field (name "PUBLISHER") "Altium Limited"))
      (libsource (lib "My Footprint") (part "RES"))
    )
    (comp (ref "R28")
      (value "33")
      (footprint "0402")
      (description "Resistor")
      (fields (field (name "PUBLISHER") "Altium Limited"))
      (libsource (lib "My Footprint") (part "RES"))
    )
    (comp (ref "R29")
      (value "33")
      (footprint "0402")
      (description "Resistor")
      (fields (field (name "PUBLISHER") "Altium Limited"))
      (libsource (lib "My Footprint") (part "RES"))
    )
    (comp (ref "R30")
      (value "33")
      (footprint "0402")
      (description "Resistor")
      (fields (field (name "PUBLISHER") "Altium Limited"))
      (libsource (lib "My Footprint") (part "RES"))
    )
    (comp (ref "R31")
      (value "33")
      (footprint "0402")
      (description "Resistor")
      (fields (field (name "PUBLISHER") "Altium Limited"))
      (libsource (lib "My Footprint") (part "RES"))
    )
    (comp (ref "R32")
      (value "33")
      (footprint "0402")
      (description "Resistor")
      (fields (field (name "PUBLISHER") "Altium Limited"))
      (libsource (lib "My Footprint") (part "RES"))
    )
    (comp (ref "R33")
      (value "47")
      (footprint "0402")
      (description "Resistor")
      (fields (field (name "PUBLISHER") "Altium Limited"))
      (libsource (lib "My Footprint") (part "RES"))
    )
    (comp (ref "R34")
      (value "180")
      (footprint "0402")
      (description "Resistor")
      (fields (field (name "PUBLISHER") "Altium Limited"))
      (libsource (lib "My Footprint") (part "RES"))
    )
    (comp (ref "R35")
      (value "180")
      (footprint "0402")
      (description "Resistor")
      (fields (field (name "PUBLISHER") "Altium Limited"))
      (libsource (lib "My Footprint") (part "RES"))
    )
    (comp (ref "R36")
      (value "47")
      (footprint "0402")
      (description "Resistor")
      (fields (field (name "PUBLISHER") "Altium Limited"))
      (libsource (lib "My Footprint") (part "RES"))
    )
    (comp (ref "R37")
      (value "430")
      (footprint "0402")
      (description "Resistor")
      (fields (field (name "PUBLISHER") "Altium Limited"))
      (libsource (lib "My Footprint") (part "RES"))
    )
    (comp (ref "R38")
      (value "47")
      (footprint "0402")
      (description "Resistor")
      (fields (field (name "PUBLISHER") "Altium Limited"))
      (libsource (lib "My Footprint") (part "RES"))
    )
    (comp (ref "R39")
      (value "180")
      (footprint "0402")
      (description "Resistor")
      (fields (field (name "PUBLISHER") "Altium Limited"))
      (libsource (lib "My Footprint") (part "RES"))
    )
    (comp (ref "R40")
      (value "180")
      (footprint "0402")
      (description "Resistor")
      (fields (field (name "PUBLISHER") "Altium Limited"))
      (libsource (lib "My Footprint") (part "RES"))
    )
    (comp (ref "R41")
      (value "47")
      (footprint "0402")
      (description "Resistor")
      (fields (field (name "PUBLISHER") "Altium Limited"))
      (libsource (lib "My Footprint") (part "RES"))
    )
    (comp (ref "R42")
      (value "430")
      (footprint "0402")
      (description "Resistor")
      (fields (field (name "PUBLISHER") "Altium Limited"))
      (libsource (lib "My Footprint") (part "RES"))
    )
    (comp (ref "R43")
      (value "47")
      (footprint "0402")
      (description "Resistor")
      (fields (field (name "PUBLISHER") "Altium Limited"))
      (libsource (lib "My Footprint") (part "RES"))
    )
    (comp (ref "R44")
      (value "180")
      (footprint "0402")
      (description "Resistor")
      (fields (field (name "PUBLISHER") "Altium Limited"))
      (libsource (lib "My Footprint") (part "RES"))
    )
    (comp (ref "R45")
      (value "180")
      (footprint "0402")
      (description "Resistor")
      (fields (field (name "PUBLISHER") "Altium Limited"))
      (libsource (lib "My Footprint") (part "RES"))
    )
    (comp (ref "R46")
      (value "47")
      (footprint "0402")
      (description "Resistor")
      (fields (field (name "PUBLISHER") "Altium Limited"))
      (libsource (lib "My Footprint") (part "RES"))
    )
    (comp (ref "R47")
      (value "430")
      (footprint "0402")
      (description "Resistor")
      (fields (field (name "PUBLISHER") "Altium Limited"))
      (libsource (lib "My Footprint") (part "RES"))
    )
    (comp (ref "R48")
      (value "47")
      (footprint "0402")
      (description "Resistor")
      (fields (field (name "PUBLISHER") "Altium Limited"))
      (libsource (lib "My Footprint") (part "RES"))
    )
    (comp (ref "R49")
      (value "180")
      (footprint "0402")
      (description "Resistor")
      (fields (field (name "PUBLISHER") "Altium Limited"))
      (libsource (lib "My Footprint") (part "RES"))
    )
    (comp (ref "R50")
      (value "180")
      (footprint "0402")
      (description "Resistor")
      (fields (field (name "PUBLISHER") "Altium Limited"))
      (libsource (lib "My Footprint") (part "RES"))
    )
    (comp (ref "R51")
      (value "47")
      (footprint "0402")
      (description "Resistor")
      (fields (field (name "PUBLISHER") "Altium Limited"))
      (libsource (lib "My Footprint") (part "RES"))
    )
    (comp (ref "R52")
      (value "430")
      (footprint "0402")
      (description "Resistor")
      (fields (field (name "PUBLISHER") "Altium Limited"))
      (libsource (lib "My Footprint") (part "RES"))
    )
    (comp (ref "R53")
      (value "49.9")
      (footprint "0402")
      (description "Resistor")
      (fields (field (name "PUBLISHER") "Altium Limited"))
      (libsource (lib "My Footprint") (part "RES"))
    )
    (comp (ref "R54")
      (value "49.9")
      (footprint "0402")
      (description "Resistor")
      (fields (field (name "PUBLISHER") "Altium Limited"))
      (libsource (lib "My Footprint") (part "RES"))
    )
    (comp (ref "R55")
      (value "49.9")
      (footprint "0402")
      (description "Resistor")
      (fields (field (name "PUBLISHER") "Altium Limited"))
      (libsource (lib "My Footprint") (part "RES"))
    )
    (comp (ref "R56")
      (value "49.9")
      (footprint "0402")
      (description "Resistor")
      (fields (field (name "PUBLISHER") "Altium Limited"))
      (libsource (lib "My Footprint") (part "RES"))
    )
    (comp (ref "R57")
      (value "430")
      (footprint "0402")
      (description "Resistor")
      (fields (field (name "PUBLISHER") "Altium Limited"))
      (libsource (lib "My Footprint") (part "RES"))
    )
    (comp (ref "R58")
      (value "430")
      (footprint "0402")
      (description "Resistor")
      (fields (field (name "PUBLISHER") "Altium Limited"))
      (libsource (lib "My Footprint") (part "RES"))
    )
    (comp (ref "R59")
      (value "430")
      (footprint "0402")
      (description "Resistor")
      (fields (field (name "PUBLISHER") "Altium Limited"))
      (libsource (lib "My Footprint") (part "RES"))
    )
    (comp (ref "R60")
      (value "430")
      (footprint "0402")
      (description "Resistor")
      (fields (field (name "PUBLISHER") "Altium Limited"))
      (libsource (lib "My Footprint") (part "RES"))
    )
    (comp (ref "R61")
      (value "18K")
      (footprint "0402")
      (description "Resistor")
      (fields (field (name "PUBLISHER") "Altium Limited"))
      (libsource (lib "My Footprint") (part "RES"))
    )
    (comp (ref "SMA1")
      (value "132414")
      (footprint "CONN_132414_AMP")
      (description "No Description Available")
      (fields (field (name "COPYRIGHT") "Copyright (C) 2022 Ultra Librarian. All rights reserved."))
      (libsource (lib "SMA_大偏脚_细针") (part "132414"))
    )
    (comp (ref "SMA2")
      (value "132414")
      (footprint "CONN_132414_AMP")
      (description "No Description Available")
      (fields (field (name "COPYRIGHT") "Copyright (C) 2022 Ultra Librarian. All rights reserved."))
      (libsource (lib "SMA_大偏脚_细针") (part "132414"))
    )
    (comp (ref "SMA3")
      (value "132414")
      (footprint "CONN_132414_AMP")
      (description "No Description Available")
      (fields (field (name "COPYRIGHT") "Copyright (C) 2022 Ultra Librarian. All rights reserved."))
      (libsource (lib "SMA_大偏脚_细针") (part "132414"))
    )
    (comp (ref "SMA4")
      (value "132414")
      (footprint "CONN_132414_AMP")
      (description "No Description Available")
      (fields (field (name "COPYRIGHT") "Copyright (C) 2022 Ultra Librarian. All rights reserved."))
      (libsource (lib "SMA_大偏脚_细针") (part "132414"))
    )
    (comp (ref "SMA5")
      (value "5-1814832-1")
      (footprint "TECO-5-1814832-1_V")
      (fields (field (name "MANUFACTURER") "TE Connectivity"))
      (libsource (lib "Altium Content Vault") (part "CN-S-4F-RF5"))
    )
    (comp (ref "SMA6")
      (value "5-1814832-1")
      (footprint "TECO-5-1814832-1_V")
      (fields (field (name "MANUFACTURER") "TE Connectivity"))
      (libsource (lib "Altium Content Vault") (part "CN-S-4F-RF5"))
    )
    (comp (ref "U1")
      (value "AD9959BCPZ")
      (footprint "ADI-CP-56-1_L")
      (description "4-Channel, 500 MSPS DDS with 10-Bit DACs, Serial, CP-56-1, 260 Tray, Pb-Free")
      (libsource (lib "AD9959") (part "CMP-0293-00014-1"))
    )
    (comp (ref "U2")
      (value "MPM3810GQB-P")
      (footprint "SamacSys:MPM3810GQB33Z")
      (description "Integrated Circuit")
      (fields (field (name "MOUSER PART NUMBER") "946-MPM3810GQBP"))
      (libsource (lib "*") (part "MPM3810GQB-P"))
    )
    (comp (ref "U3")
      (value "MP20045DQ-18")
      (footprint "SON65P300X300X100-9N")
      (description "Integrated Circuit")
      (fields (field (name "MANUFACTURER_PART_NUMBER") "MP20045DN-33-LF-Z"))
      (libsource (lib "SamacSys") (part "MP20045DN-33-LF-Z"))
    )
    (comp (ref "U4")
      (value "MP20045DQ-18")
      (footprint "SON65P300X300X100-9N")
      (description "Integrated Circuit")
      (fields (field (name "MANUFACTURER_PART_NUMBER") "MP20045DN-33-LF-Z"))
      (libsource (lib "SamacSys") (part "MP20045DN-33-LF-Z"))
    )
    (comp (ref "U5")
      (value "LM27762DSSR")
      (footprint "FP-DSS0012B-IPC_A")
      (description "IC REG CHARGE PUMP ADJ DL 12WSON")
      (libsource (lib "LM27762") (part "CMP-04918-000139-2"))
    )
    (comp (ref "U6")
      (value "OPA659")
      (footprint "DBV0005A_L")
      (fields (field (name "MANUFACTURER") "Texas Instruments") (field (name "PARTNUMBER") "OPA659IDBVT"))
      (libsource (lib "OPA659") (part "CMP-0018-00409-2"))
    )
    (comp (ref "U7")
      (value "OPA659")
      (footprint "DBV0005A_L")
      (fields (field (name "MANUFACTURER") "Texas Instruments") (field (name "PARTNUMBER") "OPA659IDBVT"))
      (libsource (lib "OPA659") (part "CMP-0018-00409-2"))
    )
    (comp (ref "U8")
      (value "OPA659")
      (footprint "DBV0005A_L")
      (fields (field (name "MANUFACTURER") "Texas Instruments") (field (name "PARTNUMBER") "OPA659IDBVT"))
      (libsource (lib "OPA659") (part "CMP-0018-00409-2"))
    )
    (comp (ref "U9")
      (value "OPA659")
      (footprint "DBV0005A_L")
      (fields (field (name "MANUFACTURER") "Texas Instruments") (field (name "PARTNUMBER") "OPA659IDBVT"))
      (libsource (lib "OPA659") (part "CMP-0018-00409-2"))
    )
    (comp (ref "U10")
      (value "OPA693IDBVR")
      (footprint "SOT95P280X145-6N")
      (description "Ultra-Wideband, Fixed Gain Video Buffer Amplifier with Disable")
      (fields (field (name "MF") "Texas Instruments"))
      (libsource (lib "OPA693") (part "OPA693IDBVR"))
    )
    (comp (ref "U11")
      (value "OPA693IDBVR")
      (footprint "SOT95P280X145-6N")
      (description "Ultra-Wideband, Fixed Gain Video Buffer Amplifier with Disable")
      (fields (field (name "MF") "Texas Instruments"))
      (libsource (lib "OPA693") (part "OPA693IDBVR"))
    )
    (comp (ref "U12")
      (value "OPA693IDBVR")
      (footprint "SOT95P280X145-6N")
      (description "Ultra-Wideband, Fixed Gain Video Buffer Amplifier with Disable")
      (fields (field (name "MF") "Texas Instruments"))
      (libsource (lib "OPA693") (part "OPA693IDBVR"))
    )
    (comp (ref "U13")
      (value "OPA693IDBVR")
      (footprint "SOT95P280X145-6N")
      (description "Ultra-Wideband, Fixed Gain Video Buffer Amplifier with Disable")
      (fields (field (name "MF") "Texas Instruments"))
      (libsource (lib "OPA693") (part "OPA693IDBVR"))
    )
    (comp (ref "XTAL1")
      (value "3225-25MHz")
      (footprint "NX3225GA-16.000M-STD-CRG-2_NDK")
      (description "No Description Available")
      (fields
        (field (name "MANUFACTURER_PART_NUMBER") "NX3225GA-16.000M-STD-CRG-2")
        (field (name "COPYRIGHT") "Copyright (C) 2022 Ultra Librarian. All rights reserved.")
      )
      (libsource (lib "3225晶振") (part "NX3225GA-16.000M-STD-CRG-2"))
    )
  )
  (nets
    (net (code "1") (name "+2.5") (class "Default")
      (node (ref "C1") (pin "2") (pinfunction "2_2") (pintype "passive"))
      (node (ref "C2") (pin "2") (pinfunction "2_2") (pintype "passive"))
      (node (ref "R4") (pin "2") (pinfunction "2_2") (pintype "passive"))
      (node (ref "R6") (pin "2") (pinfunction "2_2") (pintype "passive"))
      (node (ref "R7") (pin "2") (pinfunction "2_2") (pintype "passive"))
      (node (ref "U2") (pin "12") (pinfunction "OUT_S_12") (pintype "passive"))
      (node (ref "U2") (pin "14") (pinfunction "OUT_3_14") (pintype "passive"))
      (node (ref "U2") (pin "5") (pinfunction "OUT_1_5") (pintype "passive"))
      (node (ref "U2") (pin "6") (pinfunction "OUT_2_6") (pintype "passive"))
      (node (ref "U3") (pin "1") (pinfunction "V_IN_1") (pintype "passive"))
      (node (ref "U3") (pin "2") (pinfunction "V_IN_2") (pintype "passive"))
      (node (ref "U4") (pin "1") (pinfunction "V_IN_1") (pintype "passive"))
      (node (ref "U4") (pin "2") (pinfunction "V_IN_2") (pintype "passive"))
    )
    (net (code "2") (name "+3.3") (class "Default")
      (node (ref "C111") (pin "1") (pinfunction "1_1") (pintype "passive"))
      (node (ref "C112") (pin "1") (pinfunction "1_1") (pintype "passive"))
      (node (ref "C27") (pin "1") (pinfunction "1_1") (pintype "passive"))
      (node (ref "PMOD") (pin "19") (pinfunction "19_19") (pintype "passive"))
      (node (ref "PMOD") (pin "20") (pinfunction "20_20") (pintype "passive"))
      (node (ref "U1") (pin "49") (pinfunction "DVDD_I/O_49") (pintype "power_in"))
    )
    (net (code "3") (name "+4") (class "Default")
      (node (ref "C113") (pin "1") (pinfunction "1_1") (pintype "passive"))
      (node (ref "C114") (pin "1") (pinfunction "1_1") (pintype "passive"))
      (node (ref "C115") (pin "1") (pinfunction "1_1") (pintype "passive"))
      (node (ref "C116") (pin "1") (pinfunction "1_1") (pintype "passive"))
      (node (ref "C117") (pin "1") (pinfunction "1_1") (pintype "passive"))
      (node (ref "C118") (pin "1") (pinfunction "1_1") (pintype "passive"))
      (node (ref "C119") (pin "1") (pinfunction "1_1") (pintype "passive"))
      (node (ref "C12") (pin "1") (pinfunction "1_1") (pintype "passive"))
      (node (ref "C120") (pin "1") (pinfunction "1_1") (pintype "passive"))
      (node (ref "C76") (pin "1") (pinfunction "1_1") (pintype "passive"))
      (node (ref "C77") (pin "1") (pinfunction "1_1") (pintype "passive"))
      (node (ref "C78") (pin "1") (pinfunction "1_1") (pintype "passive"))
      (node (ref "C79") (pin "1") (pinfunction "1_1") (pintype "passive"))
      (node (ref "C80") (pin "1") (pinfunction "1_1") (pintype "passive"))
      (node (ref "C81") (pin "1") (pinfunction "1_1") (pintype "passive"))
      (node (ref "C82") (pin "1") (pinfunction "1_1") (pintype "passive"))
      (node (ref "C83") (pin "1") (pinfunction "1_1") (pintype "passive"))
      (node (ref "R13") (pin "1") (pinfunction "1_1") (pintype "passive"))
      (node (ref "U10") (pin "5") (pinfunction "~{DIS}_5") (pintype "passive"))
      (node (ref "U10") (pin "6") (pinfunction "+VS_6") (pintype "power_in"))
      (node (ref "U11") (pin "5") (pinfunction "~{DIS}_5") (pintype "passive"))
      (node (ref "U11") (pin "6") (pinfunction "+VS_6") (pintype "power_in"))
      (node (ref "U12") (pin "5") (pinfunction "~{DIS}_5") (pintype "passive"))
      (node (ref "U12") (pin "6") (pinfunction "+VS_6") (pintype "power_in"))
      (node (ref "U13") (pin "5") (pinfunction "~{DIS}_5") (pintype "passive"))
      (node (ref "U13") (pin "6") (pinfunction "+VS_6") (pintype "power_in"))
      (node (ref "U5") (pin "11") (pinfunction "OUT+_11") (pintype "passive"))
      (node (ref "U6") (pin "5") (pinfunction "VS+_5") (pintype "power_in"))
      (node (ref "U7") (pin "5") (pinfunction "VS+_5") (pintype "power_in"))
      (node (ref "U8") (pin "5") (pinfunction "VS+_5") (pintype "power_in"))
      (node (ref "U9") (pin "5") (pinfunction "VS+_5") (pintype "power_in"))
    )
    (net (code "4") (name "+5") (class "Default")
      (node (ref "C3") (pin "1") (pinfunction "1_1") (pintype "passive"))
      (node (ref "C4") (pin "1") (pinfunction "1_1") (pintype "passive"))
      (node (ref "C5") (pin "1") (pinfunction "1_1") (pintype "passive"))
      (node (ref "C9") (pin "2") (pinfunction "2_2") (pintype "passive"))
      (node (ref "FB1") (pin "2") (pinfunction "2_2") (pintype "passive"))
      (node (ref "R1") (pin "2") (pinfunction "2_2") (pintype "passive"))
      (node (ref "R10") (pin "2") (pinfunction "2_2") (pintype "passive"))
      (node (ref "R12") (pin "1") (pinfunction "1_1") (pintype "passive"))
      (node (ref "R3") (pin "2") (pinfunction "2_2") (pintype "passive"))
      (node (ref "U2") (pin "7") (pinfunction "VIN_7") (pintype "passive"))
      (node (ref "U5") (pin "3") (pinfunction "VIN_3") (pintype "power_in"))
    )
    (net (code "5") (name "-4") (class "Default")
      (node (ref "C121") (pin "1") (pinfunction "1_1") (pintype "passive"))
      (node (ref "C122") (pin "1") (pinfunction "1_1") (pintype "passive"))
      (node (ref "C123") (pin "1") (pinfunction "1_1") (pintype "passive"))
      (node (ref "C124") (pin "1") (pinfunction "1_1") (pintype "passive"))
      (node (ref "C125") (pin "1") (pinfunction "1_1") (pintype "passive"))
      (node (ref "C126") (pin "1") (pinfunction "1_1") (pintype "passive"))
      (node (ref "C127") (pin "1") (pinfunction "1_1") (pintype "passive"))
      (node (ref "C128") (pin "1") (pinfunction "1_1") (pintype "passive"))
      (node (ref "C13") (pin "2") (pinfunction "2_2") (pintype "passive"))
      (node (ref "C84") (pin "1") (pinfunction "1_1") (pintype "passive"))
      (node (ref "C85") (pin "1") (pinfunction "1_1") (pintype "passive"))
      (node (ref "C86") (pin "1") (pinfunction "1_1") (pintype "passive"))
      (node (ref "C87") (pin "1") (pinfunction "1_1") (pintype "passive"))
      (node (ref "C88") (pin "1") (pinfunction "1_1") (pintype "passive"))
      (node (ref "C89") (pin "1") (pinfunction "1_1") (pintype "passive"))
      (node (ref "C90") (pin "1") (pinfunction "1_1") (pintype "passive"))
      (node (ref "C91") (pin "1") (pinfunction "1_1") (pintype "passive"))
      (node (ref "R16") (pin "2") (pinfunction "2_2") (pintype "passive"))
      (node (ref "U10") (pin "2") (pinfunction "-VS_2") (pintype "power_in"))
      (node (ref "U11") (pin "2") (pinfunction "-VS_2") (pintype "power_in"))
      (node (ref "U12") (pin "2") (pinfunction "-VS_2") (pintype "power_in"))
      (node (ref "U13") (pin "2") (pinfunction "-VS_2") (pintype "power_in"))
      (node (ref "U5") (pin "6") (pinfunction "OUT-_6") (pintype "passive"))
      (node (ref "U6") (pin "2") (pinfunction "VS-_2") (pintype "power_in"))
      (node (ref "U7") (pin "2") (pinfunction "VS-_2") (pintype "power_in"))
      (node (ref "U8") (pin "2") (pinfunction "VS-_2") (pintype "power_in"))
      (node (ref "U9") (pin "2") (pinfunction "VS-_2") (pintype "power_in"))
    )
    (net (code "6") (name "/CH0+") (class "Default")
      (node (ref "C39") (pin "2") (pinfunction "2_2") (pintype "passive"))
      (node (ref "R33") (pin "2") (pinfunction "2_2") (pintype "passive"))
      (node (ref "R34") (pin "1") (pinfunction "1_1") (pintype "passive"))
      (node (ref "U1") (pin "30") (pinfunction "CH0_IOUT_30") (pintype "output"))
    )
    (net (code "7") (name "/CH0-") (class "Default")
      (node (ref "C39") (pin "1") (pinfunction "1_1") (pintype "passive"))
      (node (ref "R35") (pin "1") (pinfunction "1_1") (pintype "passive"))
      (node (ref "R36") (pin "1") (pinfunction "1_1") (pintype "passive"))
      (node (ref "U1") (pin "29") (pinfunction "~{CH0_IOUT}_29") (pintype "output"))
    )
    (net (code "8") (name "/CH0_OUT") (class "Default")
      (node (ref "C131") (pin "2") (pinfunction "2_2") (pintype "passive"))
      (node (ref "R53") (pin "2") (pinfunction "2_2") (pintype "passive"))
      (node (ref "SMA1") (pin "1") (pinfunction "1_1") (pintype "passive"))
    )
    (net (code "9") (name "/CH1+") (class "Default")
      (node (ref "C51") (pin "2") (pinfunction "2_2") (pintype "passive"))
      (node (ref "R38") (pin "2") (pinfunction "2_2") (pintype "passive"))
      (node (ref "R39") (pin "1") (pinfunction "1_1") (pintype "passive"))
      (node (ref "U1") (pin "36") (pinfunction "CH1_IOUT_36") (pintype "output"))
    )
    (net (code "10") (name "/CH1-") (class "Default")
      (node (ref "C51") (pin "1") (pinfunction "1_1") (pintype "passive"))
      (node (ref "R40") (pin "1") (pinfunction "1_1") (pintype "passive"))
      (node (ref "R41") (pin "1") (pinfunction "1_1") (pintype "passive"))
      (node (ref "U1") (pin "35") (pinfunction "~{CH1_IOUT}_35") (pintype "output"))
    )
    (net (code "11") (name "/CH1_OUT") (class "Default")
      (node (ref "C132") (pin "2") (pinfunction "2_2") (pintype "passive"))
      (node (ref "R54") (pin "2") (pinfunction "2_2") (pintype "passive"))
      (node (ref "SMA2") (pin "1") (pinfunction "1_1") (pintype "passive"))
    )
    (net (code "12") (name "/CH2+") (class "Default")
      (node (ref "C63") (pin "1") (pinfunction "1_1") (pintype "passive"))
      (node (ref "R45") (pin "1") (pinfunction "1_1") (pintype "passive"))
      (node (ref "R46") (pin "1") (pinfunction "1_1") (pintype "passive"))
      (node (ref "U1") (pin "8") (pinfunction "CH2_IOUT_8") (pintype "output"))
    )
    (net (code "13") (name "/CH2-") (class "Default")
      (node (ref "C63") (pin "2") (pinfunction "2_2") (pintype "passive"))
      (node (ref "R43") (pin "2") (pinfunction "2_2") (pintype "passive"))
      (node (ref "R44") (pin "1") (pinfunction "1_1") (pintype "passive"))
      (node (ref "U1") (pin "9") (pinfunction "~{CH2_IOUT}_9") (pintype "output"))
    )
    (net (code "14") (name "/CH2_OUT") (class "Default")
      (node (ref "C133") (pin "2") (pinfunction "2_2") (pintype "passive"))
      (node (ref "R55") (pin "2") (pinfunction "2_2") (pintype "passive"))
      (node (ref "SMA3") (pin "1") (pinfunction "1_1") (pintype "passive"))
    )
    (net (code "15") (name "/CH3+") (class "Default")
      (node (ref "C75") (pin "1") (pinfunction "1_1") (pintype "passive"))
      (node (ref "R50") (pin "1") (pinfunction "1_1") (pintype "passive"))
      (node (ref "R51") (pin "1") (pinfunction "1_1") (pintype "passive"))
      (node (ref "U1") (pin "13") (pinfunction "CH3_IOUT_13") (pintype "output"))
    )
    (net (code "16") (name "/CH3-") (class "Default")
      (node (ref "C75") (pin "2") (pinfunction "2_2") (pintype "passive"))
      (node (ref "R48") (pin "2") (pinfunction "2_2") (pintype "passive"))
      (node (ref "R49") (pin "1") (pinfunction "1_1") (pintype "passive"))
      (node (ref "U1") (pin "14") (pinfunction "~{CH3_IOUT}_14") (pintype "output"))
    )
    (net (code "17") (name "/CH3_OUT") (class "Default")
      (node (ref "C134") (pin "2") (pinfunction "2_2") (pintype "passive"))
      (node (ref "R56") (pin "2") (pinfunction "2_2") (pintype "passive"))
      (node (ref "SMA4") (pin "1") (pinfunction "1_1") (pintype "passive"))
    )
    (net (code "18") (name "/CLK+") (class "Default")
      (node (ref "C129") (pin "2") (pinfunction "2_2") (pintype "passive"))
      (node (ref "R31") (pin "2") (pinfunction "2_2") (pintype "passive"))
      (node (ref "U1") (pin "23") (pinfunction "REF_CLK_23") (pintype "input"))
      (node (ref "XTAL1") (pin "1") (pinfunction "1_1") (pintype "passive"))
    )
    (net (code "19") (name "/CLK-") (class "Default")
      (node (ref "C130") (pin "2") (pinfunction "2_2") (pintype "passive"))
      (node (ref "R32") (pin "1") (pinfunction "1_1") (pintype "passive"))
      (node (ref "U1") (pin "22") (pinfunction "~{REF_CLK}_22") (pintype "input"))
      (node (ref "XTAL1") (pin "3") (pinfunction "3_3") (pintype "passive"))
    )
    (net (code "20") (name "/CLK_MODE") (class "Default")
      (node (ref "R2") (pin "1") (pinfunction "1_1") (pintype "passive"))
      (node (ref "U1") (pin "24") (pinfunction "CLK_MODE_SEL_24") (pintype "input"))
    )
    (net (code "21") (name "/CS") (class "Default")
      (node (ref "R21") (pin "2") (pinfunction "2_2") (pintype "passive"))
      (node (ref "U1") (pin "47") (pinfunction "~{CS}_47") (pintype "input"))
    )
    (net (code "22") (name "/I{slash}O_UPDATE") (class "Default")
      (node (ref "R22") (pin "1") (pinfunction "1_1") (pintype "passive"))
      (node (ref "U1") (pin "46") (pinfunction "I/O_UPDATE_46") (pintype "input"))
    )
    (net (code "23") (name "/P0") (class "Default")
      (node (ref "R18") (pin "1") (pinfunction "1_1") (pintype "passive"))
      (node (ref "U1") (pin "40") (pinfunction "P0_40") (pintype "input"))
    )
    (net (code "24") (name "/P1") (class "Default")
      (node (ref "R17") (pin "2") (pinfunction "2_2") (pintype "passive"))
      (node (ref "U1") (pin "41") (pinfunction "P1_41") (pintype "input"))
    )
    (net (code "25") (name "/P2") (class "Default")
      (node (ref "R20") (pin "1") (pinfunction "1_1") (pintype "passive"))
      (node (ref "U1") (pin "42") (pinfunction "P2_42") (pintype "input"))
    )
    (net (code "26") (name "/P3") (class "Default")
      (node (ref "R19") (pin "2") (pinfunction "2_2") (pintype "passive"))
      (node (ref "U1") (pin "43") (pinfunction "P3_43") (pintype "input"))
    )
    (net (code "27") (name "/PG_1") (class "Default")
      (node (ref "D1") (pin "2") (pinfunction "K_2") (pintype "passive"))
      (node (ref "U2") (pin "8") (pinfunction "PG_8") (pintype "passive"))
      (node (ref "U3") (pin "7") (pinfunction "PG_7") (pintype "passive"))
      (node (ref "U4") (pin "7") (pinfunction "PG_7") (pintype "passive"))
    )
    (net (code "28") (name "/PWR_DOWN") (class "Default")
      (node (ref "R29") (pin "2") (pinfunction "2_2") (pintype "passive"))
      (node (ref "U1") (pin "4") (pinfunction "PWR_DWN_CTL_4") (pintype "input"))
    )
    (net (code "29") (name "/RESET") (class "Default")
      (node (ref "R30") (pin "1") (pinfunction "1_1") (pintype "passive"))
      (node (ref "U1") (pin "3") (pinfunction "MASTER_RESET_3") (pintype "input"))
    )
    (net (code "30") (name "/SCLK") (class "Default")
      (node (ref "R24") (pin "1") (pinfunction "1_1") (pintype "passive"))
      (node (ref "U1") (pin "48") (pinfunction "SCLK_48") (pintype "input"))
    )
    (net (code "31") (name "/SDIO_0") (class "Default")
      (node (ref "R23") (pin "2") (pinfunction "2_2") (pintype "passive"))
      (node (ref "U1") (pin "50") (pinfunction "SDIO_0_50") (pintype "bidirectional"))
    )
    (net (code "32") (name "/SDIO_1") (class "Default")
      (node (ref "R26") (pin "1") (pinfunction "1_1") (pintype "passive"))
      (node (ref "U1") (pin "51") (pinfunction "SDIO_1_51") (pintype "bidirectional"))
    )
    (net (code "33") (name "/SDIO_2") (class "Default")
      (node (ref "R25") (pin "2") (pinfunction "2_2") (pintype "passive"))
      (node (ref "U1") (pin "52") (pinfunction "SDIO_2_52") (pintype "bidirectional"))
    )
    (net (code "34") (name "/SDIO_3") (class "Default")
      (node (ref "R28") (pin "1") (pinfunction "1_1") (pintype "passive"))
      (node (ref "U1") (pin "53") (pinfunction "SDIO_3_53") (pintype "bidirectional"))
    )
    (net (code "35") (name "/SYNC_CLK") (class "Default")
      (node (ref "R27") (pin "2") (pinfunction "2_2") (pintype "passive"))
      (node (ref "U1") (pin "54") (pinfunction "SYNC_CLK_54") (pintype "output"))
    )
    (net (code "36") (name "/SYNC_IN") (class "Default")
      (node (ref "SMA5") (pin "1") (pinfunction "1_1") (pintype "passive"))
      (node (ref "U1") (pin "1") (pinfunction "SYNC_IN_1") (pintype "input"))
    )
    (net (code "37") (name "/SYNC_OUT") (class "Default")
      (node (ref "SMA6") (pin "1") (pinfunction "1_1") (pintype "passive"))
      (node (ref "U1") (pin "2") (pinfunction "SYNC_OUT_2") (pintype "output"))
    )
    (net (code "38") (name "A+1.8") (class "Default")
      (node (ref "C100") (pin "1") (pinfunction "1_1") (pintype "passive"))
      (node (ref "C101") (pin "1") (pinfunction "1_1") (pintype "passive"))
      (node (ref "C102") (pin "1") (pinfunction "1_1") (pintype "passive"))
      (node (ref "C103") (pin "1") (pinfunction "1_1") (pintype "passive"))
      (node (ref "C104") (pin "1") (pinfunction "1_1") (pintype "passive"))
      (node (ref "C105") (pin "1") (pinfunction "1_1") (pintype "passive"))
      (node (ref "C106") (pin "1") (pinfunction "1_1") (pintype "passive"))
      (node (ref "C107") (pin "1") (pinfunction "1_1") (pintype "passive"))
      (node (ref "C108") (pin "1") (pinfunction "1_1") (pintype "passive"))
      (node (ref "C109") (pin "1") (pinfunction "1_1") (pintype "passive"))
      (node (ref "C110") (pin "1") (pinfunction "1_1") (pintype "passive"))
      (node (ref "C16") (pin "1") (pinfunction "1_1") (pintype "passive"))
      (node (ref "C17") (pin "1") (pinfunction "1_1") (pintype "passive"))
      (node (ref "C18") (pin "1") (pinfunction "1_1") (pintype "passive"))
      (node (ref "C19") (pin "1") (pinfunction "1_1") (pintype "passive"))
      (node (ref "C20") (pin "1") (pinfunction "1_1") (pintype "passive"))
      (node (ref "C21") (pin "1") (pinfunction "1_1") (pintype "passive"))
      (node (ref "C22") (pin "1") (pinfunction "1_1") (pintype "passive"))
      (node (ref "C23") (pin "1") (pinfunction "1_1") (pintype "passive"))
      (node (ref "C24") (pin "1") (pinfunction "1_1") (pintype "passive"))
      (node (ref "C25") (pin "1") (pinfunction "1_1") (pintype "passive"))
      (node (ref "C26") (pin "1") (pinfunction "1_1") (pintype "passive"))
      (node (ref "C8") (pin "1") (pinfunction "1_1") (pintype "passive"))
      (node (ref "C95") (pin "1") (pinfunction "1_1") (pintype "passive"))
      (node (ref "C96") (pin "1") (pinfunction "1_1") (pintype "passive"))
      (node (ref "C97") (pin "1") (pinfunction "1_1") (pintype "passive"))
      (node (ref "C98") (pin "1") (pinfunction "1_1") (pintype "passive"))
      (node (ref "C99") (pin "1") (pinfunction "1_1") (pintype "passive"))
      (node (ref "CLK_MODE") (pin "1") (pinfunction "1_1") (pintype "passive"))
      (node (ref "R33") (pin "1") (pinfunction "1_1") (pintype "passive"))
      (node (ref "R36") (pin "2") (pinfunction "2_2") (pintype "passive"))
      (node (ref "R38") (pin "1") (pinfunction "1_1") (pintype "passive"))
      (node (ref "R41") (pin "2") (pinfunction "2_2") (pintype "passive"))
      (node (ref "R43") (pin "1") (pinfunction "1_1") (pintype "passive"))
      (node (ref "R46") (pin "2") (pinfunction "2_2") (pintype "passive"))
      (node (ref "R48") (pin "1") (pinfunction "1_1") (pintype "passive"))
      (node (ref "R51") (pin "2") (pinfunction "2_2") (pintype "passive"))
      (node (ref "U1") (pin "11") (pinfunction "AVDD_11") (pintype "power_in"))
      (node (ref "U1") (pin "15") (pinfunction "AVDD_15") (pintype "power_in"))
      (node (ref "U1") (pin "19") (pinfunction "AVDD_19") (pintype "power_in"))
      (node (ref "U1") (pin "21") (pinfunction "AVDD_21") (pintype "power_in"))
      (node (ref "U1") (pin "26") (pinfunction "AVDD_26") (pintype "power_in"))
      (node (ref "U1") (pin "31") (pinfunction "AVDD_31") (pintype "power_in"))
      (node (ref "U1") (pin "33") (pinfunction "AVDD_33") (pintype "power_in"))
      (node (ref "U1") (pin "37") (pinfunction "AVDD_37") (pintype "power_in"))
      (node (ref "U1") (pin "39") (pinfunction "AVDD_39") (pintype "power_in"))
      (node (ref "U1") (pin "5") (pinfunction "AVDD_5") (pintype "power_in"))
      (node (ref "U1") (pin "7") (pinfunction "AVDD_7") (pintype "power_in"))
      (node (ref "U3") (pin "3") (pinfunction "V_OUT_3") (pintype "passive"))
      (node (ref "U3") (pin "4") (pinfunction "V_OUT_4") (pintype "passive"))
      (node (ref "U3") (pin "5") (pinfunction "FB_5") (pintype "passive"))
    )
    (net (code "39") (name "D+1.8") (class "Default")
      (node (ref "C14") (pin "1") (pinfunction "1_1") (pintype "passive"))
      (node (ref "C15") (pin "1") (pinfunction "1_1") (pintype "passive"))
      (node (ref "C7") (pin "1") (pinfunction "1_1") (pintype "passive"))
      (node (ref "U1") (pin "45") (pinfunction "DVDD_45") (pintype "power_in"))
      (node (ref "U1") (pin "55") (pinfunction "DVDD_55") (pintype "power_in"))
      (node (ref "U4") (pin "3") (pinfunction "V_OUT_3") (pintype "passive"))
      (node (ref "U4") (pin "4") (pinfunction "V_OUT_4") (pintype "passive"))
      (node (ref "U4") (pin "5") (pinfunction "FB_5") (pintype "passive"))
    )
    (net (code "40") (name "GND") (class "Default")
      (node (ref "C1") (pin "1") (pinfunction "1_1") (pintype "passive"))
      (node (ref "C100") (pin "2") (pinfunction "2_2") (pintype "passive"))
      (node (ref "C101") (pin "2") (pinfunction "2_2") (pintype "passive"))
      (node (ref "C102") (pin "2") (pinfunction "2_2") (pintype "passive"))
      (node (ref "C103") (pin "2") (pinfunction "2_2") (pintype "passive"))
      (node (ref "C104") (pin "2") (pinfunction "2_2") (pintype "passive"))
      (node (ref "C105") (pin "2") (pinfunction "2_2") (pintype "passive"))
      (node (ref "C106") (pin "2") (pinfunction "2_2") (pintype "passive"))
      (node (ref "C107") (pin "2") (pinfunction "2_2") (pintype "passive"))
      (node (ref "C108") (pin "2") (pinfunction "2_2") (pintype "passive"))
      (node (ref "C109") (pin "2") (pinfunction "2_2") (pintype "passive"))
      (node (ref "C11") (pin "2") (pinfunction "2_2") (pintype "passive"))
      (node (ref "C110") (pin "2") (pinfunction "2_2") (pintype "passive"))
      (node (ref "C111") (pin "2") (pinfunction "2_2") (pintype "passive"))
      (node (ref "C112") (pin "2") (pinfunction "2_2") (pintype "passive"))
      (node (ref "C113") (pin "2") (pinfunction "2_2") (pintype "passive"))
      (node (ref "C114") (pin "2") (pinfunction "2_2") (pintype "passive"))
      (node (ref "C115") (pin "2") (pinfunction "2_2") (pintype "passive"))
      (node (ref "C116") (pin "2") (pinfunction "2_2") (pintype "passive"))
      (node (ref "C117") (pin "2") (pinfunction "2_2") (pintype "passive"))
      (node (ref "C118") (pin "2") (pinfunction "2_2") (pintype "passive"))
      (node (ref "C119") (pin "2") (pinfunction "2_2") (pintype "passive"))
      (node (ref "C12") (pin "2") (pinfunction "2_2") (pintype "passive"))
      (node (ref "C120") (pin "2") (pinfunction "2_2") (pintype "passive"))
      (node (ref "C121") (pin "2") (pinfunction "2_2") (pintype "passive"))
      (node (ref "C122") (pin "2") (pinfunction "2_2") (pintype "passive"))
      (node (ref "C123") (pin "2") (pinfunction "2_2") (pintype "passive"))
      (node (ref "C124") (pin "2") (pinfunction "2_2") (pintype "passive"))
      (node (ref "C125") (pin "2") (pinfunction "2_2") (pintype "passive"))
      (node (ref "C126") (pin "2") (pinfunction "2_2") (pintype "passive"))
      (node (ref "C127") (pin "2") (pinfunction "2_2") (pintype "passive"))
      (node (ref "C128") (pin "2") (pinfunction "2_2") (pintype "passive"))
      (node (ref "C129") (pin "1") (pinfunction "1_1") (pintype "passive"))
      (node (ref "C13") (pin "1") (pinfunction "1_1") (pintype "passive"))
      (node (ref "C130") (pin "1") (pinfunction "1_1") (pintype "passive"))
      (node (ref "C14") (pin "2") (pinfunction "2_2") (pintype "passive"))
      (node (ref "C15") (pin "2") (pinfunction "2_2") (pintype "passive"))
      (node (ref "C16") (pin "2") (pinfunction "2_2") (pintype "passive"))
      (node (ref "C17") (pin "2") (pinfunction "2_2") (pintype "passive"))
      (node (ref "C18") (pin "2") (pinfunction "2_2") (pintype "passive"))
      (node (ref "C19") (pin "2") (pinfunction "2_2") (pintype "passive"))
      (node (ref "C2") (pin "1") (pinfunction "1_1") (pintype "passive"))
      (node (ref "C20") (pin "2") (pinfunction "2_2") (pintype "passive"))
      (node (ref "C21") (pin "2") (pinfunction "2_2") (pintype "passive"))
      (node (ref "C22") (pin "2") (pinfunction "2_2") (pintype "passive"))
      (node (ref "C23") (pin "2") (pinfunction "2_2") (pintype "passive"))
      (node (ref "C24") (pin "2") (pinfunction "2_2") (pintype "passive"))
      (node (ref "C25") (pin "2") (pinfunction "2_2") (pintype "passive"))
      (node (ref "C26") (pin "2") (pinfunction "2_2") (pintype "passive"))
      (node (ref "C27") (pin "2") (pinfunction "2_2") (pintype "passive"))
      (node (ref "C28") (pin "1") (pinfunction "1_1") (pintype "passive"))
      (node (ref "C3") (pin "2") (pinfunction "2_2") (pintype "passive"))
      (node (ref "C30") (pin "1") (pinfunction "1_1") (pintype "passive"))
      (node (ref "C32") (pin "1") (pinfunction "1_1") (pintype "passive"))
      (node (ref "C34") (pin "2") (pinfunction "2_2") (pintype "passive"))
      (node (ref "C35") (pin "2") (pinfunction "2_2") (pintype "passive"))
      (node (ref "C36") (pin "2") (pinfunction "2_2") (pintype "passive"))
      (node (ref "C37") (pin "2") (pinfunction "2_2") (pintype "passive"))
      (node (ref "C38") (pin "1") (pinfunction "1_1") (pintype "passive"))
      (node (ref "C4") (pin "2") (pinfunction "2_2") (pintype "passive"))
      (node (ref "C40") (pin "1") (pinfunction "1_1") (pintype "passive"))
      (node (ref "C42") (pin "1") (pinfunction "1_1") (pintype "passive"))
      (node (ref "C44") (pin "1") (pinfunction "1_1") (pintype "passive"))
      (node (ref "C46") (pin "2") (pinfunction "2_2") (pintype "passive"))
      (node (ref "C47") (pin "2") (pinfunction "2_2") (pintype "passive"))
      (node (ref "C48") (pin "2") (pinfunction "2_2") (pintype "passive"))
      (node (ref "C49") (pin "2") (pinfunction "2_2") (pintype "passive"))
      (node (ref "C5") (pin "2") (pinfunction "2_2") (pintype "passive"))
      (node (ref "C50") (pin "1") (pinfunction "1_1") (pintype "passive"))
      (node (ref "C52") (pin "1") (pinfunction "1_1") (pintype "passive"))
      (node (ref "C54") (pin "1") (pinfunction "1_1") (pintype "passive"))
      (node (ref "C56") (pin "1") (pinfunction "1_1") (pintype "passive"))
      (node (ref "C58") (pin "2") (pinfunction "2_2") (pintype "passive"))
      (node (ref "C59") (pin "2") (pinfunction "2_2") (pintype "passive"))
      (node (ref "C6") (pin "1") (pinfunction "1_1") (pintype "passive"))
      (node (ref "C60") (pin "2") (pinfunction "2_2") (pintype "passive"))
      (node (ref "C61") (pin "2") (pinfunction "2_2") (pintype "passive"))
      (node (ref "C62") (pin "1") (pinfunction "1_1") (pintype "passive"))
      (node (ref "C64") (pin "1") (pinfunction "1_1") (pintype "passive"))
      (node (ref "C66") (pin "1") (pinfunction "1_1") (pintype "passive"))
      (node (ref "C68") (pin "1") (pinfunction "1_1") (pintype "passive"))
      (node (ref "C7") (pin "2") (pinfunction "2_2") (pintype "passive"))
      (node (ref "C70") (pin "2") (pinfunction "2_2") (pintype "passive"))
      (node (ref "C71") (pin "2") (pinfunction "2_2") (pintype "passive"))
      (node (ref "C72") (pin "2") (pinfunction "2_2") (pintype "passive"))
      (node (ref "C73") (pin "2") (pinfunction "2_2") (pintype "passive"))
      (node (ref "C74") (pin "1") (pinfunction "1_1") (pintype "passive"))
      (node (ref "C76") (pin "2") (pinfunction "2_2") (pintype "passive"))
      (node (ref "C77") (pin "2") (pinfunction "2_2") (pintype "passive"))
      (node (ref "C78") (pin "2") (pinfunction "2_2") (pintype "passive"))
      (node (ref "C79") (pin "2") (pinfunction "2_2") (pintype "passive"))
      (node (ref "C8") (pin "2") (pinfunction "2_2") (pintype "passive"))
      (node (ref "C80") (pin "2") (pinfunction "2_2") (pintype "passive"))
      (node (ref "C81") (pin "2") (pinfunction "2_2") (pintype "passive"))
      (node (ref "C82") (pin "2") (pinfunction "2_2") (pintype "passive"))
      (node (ref "C83") (pin "2") (pinfunction "2_2") (pintype "passive"))
      (node (ref "C84") (pin "2") (pinfunction "2_2") (pintype "passive"))
      (node (ref "C85") (pin "2") (pinfunction "2_2") (pintype "passive"))
      (node (ref "C86") (pin "2") (pinfunction "2_2") (pintype "passive"))
      (node (ref "C87") (pin "2") (pinfunction "2_2") (pintype "passive"))
      (node (ref "C88") (pin "2") (pinfunction "2_2") (pintype "passive"))
      (node (ref "C89") (pin "2") (pinfunction "2_2") (pintype "passive"))
      (node (ref "C9") (pin "1") (pinfunction "1_1") (pintype "passive"))
      (node (ref "C90") (pin "2") (pinfunction "2_2") (pintype "passive"))
      (node (ref "C91") (pin "2") (pinfunction "2_2") (pintype "passive"))
      (node (ref "C92") (pin "2") (pinfunction "2_2") (pintype "passive"))
      (node (ref "C93") (pin "2") (pinfunction "2_2") (pintype "passive"))
      (node (ref "C94") (pin "2") (pinfunction "2_2") (pintype "passive"))
      (node (ref "C95") (pin "2") (pinfunction "2_2") (pintype "passive"))
      (node (ref "C96") (pin "2") (pinfunction "2_2") (pintype "passive"))
      (node (ref "C97") (pin "2") (pinfunction "2_2") (pintype "passive"))
      (node (ref "C98") (pin "2") (pinfunction "2_2") (pintype "passive"))
      (node (ref "C99") (pin "2") (pinfunction "2_2") (pintype "passive"))
      (node (ref "CLK_MODE") (pin "3") (pinfunction "3_3") (pintype "passive"))
      (node (ref "D2") (pin "2") (pinfunction "K_2") (pintype "passive"))
      (node (ref "D3") (pin "2") (pinfunction "K_2") (pintype "passive"))
      (node (ref "PMOD") (pin "17") (pinfunction "17_17") (pintype "passive"))
      (node (ref "PMOD") (pin "18") (pinfunction "18_18") (pintype "passive"))
      (node (ref "POWER") (pin "1") (pinfunction "1_1") (pintype "passive"))
      (node (ref "R14") (pin "1") (pinfunction "1_1") (pintype "passive"))
      (node (ref "R15") (pin "1") (pinfunction "1_1") (pintype "passive"))
      (node (ref "R5") (pin "1") (pinfunction "1_1") (pintype "passive"))
      (node (ref "R57") (pin "2") (pinfunction "2_2") (pintype "passive"))
      (node (ref "R58") (pin "2") (pinfunction "2_2") (pintype "passive"))
      (node (ref "R59") (pin "2") (pinfunction "2_2") (pintype "passive"))
      (node (ref "R60") (pin "2") (pinfunction "2_2") (pintype "passive"))
      (node (ref "R9") (pin "2") (pinfunction "2_2") (pintype "passive"))
      (node (ref "SMA1") (pin "2") (pinfunction "2_2") (pintype "passive"))
      (node (ref "SMA1") (pin "3") (pinfunction "3_3") (pintype "passive"))
      (node (ref "SMA1") (pin "4") (pinfunction "4_4") (pintype "passive"))
      (node (ref "SMA2") (pin "2") (pinfunction "2_2") (pintype "passive"))
      (node (ref "SMA2") (pin "3") (pinfunction "3_3") (pintype "passive"))
      (node (ref "SMA2") (pin "4") (pinfunction "4_4") (pintype "passive"))
      (node (ref "SMA3") (pin "2") (pinfunction "2_2") (pintype "passive"))
      (node (ref "SMA3") (pin "3") (pinfunction "3_3") (pintype "passive"))
      (node (ref "SMA3") (pin "4") (pinfunction "4_4") (pintype "passive"))
      (node (ref "SMA4") (pin "2") (pinfunction "2_2") (pintype "passive"))
      (node (ref "SMA4") (pin "3") (pinfunction "3_3") (pintype "passive"))
      (node (ref "SMA4") (pin "4") (pinfunction "4_4") (pintype "passive"))
      (node (ref "SMA5") (pin "2") (pinfunction "2_2") (pintype "passive"))
      (node (ref "SMA5") (pin "3") (pinfunction "3_3") (pintype "passive"))
      (node (ref "SMA5") (pin "4") (pinfunction "4_4") (pintype "passive"))
      (node (ref "SMA5") (pin "5") (pinfunction "5_5") (pintype "passive"))
      (node (ref "SMA6") (pin "2") (pinfunction "2_2") (pintype "passive"))
      (node (ref "SMA6") (pin "3") (pinfunction "3_3") (pintype "passive"))
      (node (ref "SMA6") (pin "4") (pinfunction "4_4") (pintype "passive"))
      (node (ref "SMA6") (pin "5") (pinfunction "5_5") (pintype "passive"))
      (node (ref "U1") (pin "10") (pinfunction "AGND_10") (pintype "power_in"))
      (node (ref "U1") (pin "12") (pinfunction "AGND_12") (pintype "power_in"))
      (node (ref "U1") (pin "16") (pinfunction "AGND_16") (pintype "power_in"))
      (node (ref "U1") (pin "18") (pinfunction "AGND_18") (pintype "power_in"))
      (node (ref "U1") (pin "20") (pinfunction "AGND_20") (pintype "power_in"))
      (node (ref "U1") (pin "25") (pinfunction "AGND_25") (pintype "power_in"))
      (node (ref "U1") (pin "28") (pinfunction "AGND_28") (pintype "power_in"))
      (node (ref "U1") (pin "32") (pinfunction "AGND_32") (pintype "power_in"))
      (node (ref "U1") (pin "34") (pinfunction "AGND_34") (pintype "power_in"))
      (node (ref "U1") (pin "38") (pinfunction "AGND_38") (pintype "power_in"))
      (node (ref "U1") (pin "44") (pinfunction "DGND_44") (pintype "power_in"))
      (node (ref "U1") (pin "56") (pinfunction "DGND_56") (pintype "power_in"))
      (node (ref "U1") (pin "57") (pinfunction "EP_57") (pintype "power_in"))
      (node (ref "U1") (pin "6") (pinfunction "AGND_6") (pintype "power_in"))
      (node (ref "U10") (pin "4") (pinfunction "-IN_4") (pintype "input"))
      (node (ref "U11") (pin "4") (pinfunction "-IN_4") (pintype "input"))
      (node (ref "U12") (pin "4") (pinfunction "-IN_4") (pintype "input"))
      (node (ref "U13") (pin "4") (pinfunction "-IN_4") (pintype "input"))
      (node (ref "U2") (pin "1") (pinfunction "PGND_1_1") (pintype "passive"))
      (node (ref "U2") (pin "11") (pinfunction "AGND_11") (pintype "passive"))
      (node (ref "U2") (pin "2") (pinfunction "PGND_2_2") (pintype "passive"))
      (node (ref "U3") (pin "6") (pinfunction "GND_6") (pintype "passive"))
      (node (ref "U3") (pin "9") (pinfunction "EP_9") (pintype "passive"))
      (node (ref "U4") (pin "6") (pinfunction "GND_6") (pintype "passive"))
      (node (ref "U4") (pin "9") (pinfunction "EP_9") (pintype "passive"))
      (node (ref "U5") (pin "13") (pinfunction "Thermal_Pad_13") (pintype "passive"))
      (node (ref "U5") (pin "4") (pinfunction "GND_4") (pintype "power_in"))
      (node (ref "XTAL1") (pin "2") (pinfunction "2_2") (pintype "passive"))
      (node (ref "XTAL1") (pin "4") (pinfunction "4_4") (pintype "passive"))
    )
    (net (code "41") (name "Net-(C6-Pad2)") (class "Default")
      (node (ref "C6") (pin "2") (pinfunction "2_2") (pintype "passive"))
      (node (ref "R8") (pin "2") (pinfunction "2_2") (pintype "passive"))
    )
    (net (code "42") (name "Net-(C29-Pad2)") (class "Default")
      (node (ref "C29") (pin "2") (pinfunction "2_2") (pintype "passive"))
      (node (ref "C30") (pin "2") (pinfunction "2_2") (pintype "passive"))
      (node (ref "C31") (pin "1") (pinfunction "1_1") (pintype "passive"))
      (node (ref "C36") (pin "1") (pinfunction "1_1") (pintype "passive"))
      (node (ref "L1") (pin "1") (pinfunction "1_1") (pintype "passive"))
      (node (ref "L2") (pin "2") (pinfunction "2_2") (pintype "passive"))
    )
    (net (code "43") (name "Net-(C31-Pad2)") (class "Default")
      (node (ref "C31") (pin "2") (pinfunction "2_2") (pintype "passive"))
      (node (ref "C32") (pin "2") (pinfunction "2_2") (pintype "passive"))
      (node (ref "C33") (pin "1") (pinfunction "1_1") (pintype "passive"))
      (node (ref "C37") (pin "1") (pinfunction "1_1") (pintype "passive"))
      (node (ref "L2") (pin "1") (pinfunction "1_1") (pintype "passive"))
      (node (ref "L3") (pin "2") (pinfunction "2_2") (pintype "passive"))
    )
    (net (code "44") (name "Net-(C41-Pad2)") (class "Default")
      (node (ref "C41") (pin "2") (pinfunction "2_2") (pintype "passive"))
      (node (ref "C42") (pin "2") (pinfunction "2_2") (pintype "passive"))
      (node (ref "C43") (pin "1") (pinfunction "1_1") (pintype "passive"))
      (node (ref "C48") (pin "1") (pinfunction "1_1") (pintype "passive"))
      (node (ref "L4") (pin "1") (pinfunction "1_1") (pintype "passive"))
      (node (ref "L5") (pin "2") (pinfunction "2_2") (pintype "passive"))
    )
    (net (code "45") (name "Net-(C43-Pad2)") (class "Default")
      (node (ref "C43") (pin "2") (pinfunction "2_2") (pintype "passive"))
      (node (ref "C44") (pin "2") (pinfunction "2_2") (pintype "passive"))
      (node (ref "C45") (pin "1") (pinfunction "1_1") (pintype "passive"))
      (node (ref "C49") (pin "1") (pinfunction "1_1") (pintype "passive"))
      (node (ref "L5") (pin "1") (pinfunction "1_1") (pintype "passive"))
      (node (ref "L6") (pin "2") (pinfunction "2_2") (pintype "passive"))
    )
    (net (code "46") (name "Net-(C53-Pad2)") (class "Default")
      (node (ref "C53") (pin "2") (pinfunction "2_2") (pintype "passive"))
      (node (ref "C54") (pin "2") (pinfunction "2_2") (pintype "passive"))
      (node (ref "C55") (pin "1") (pinfunction "1_1") (pintype "passive"))
      (node (ref "C60") (pin "1") (pinfunction "1_1") (pintype "passive"))
      (node (ref "L7") (pin "1") (pinfunction "1_1") (pintype "passive"))
      (node (ref "L8") (pin "2") (pinfunction "2_2") (pintype "passive"))
    )
    (net (code "47") (name "Net-(C55-Pad2)") (class "Default")
      (node (ref "C55") (pin "2") (pinfunction "2_2") (pintype "passive"))
      (node (ref "C56") (pin "2") (pinfunction "2_2") (pintype "passive"))
      (node (ref "C57") (pin "1") (pinfunction "1_1") (pintype "passive"))
      (node (ref "C61") (pin "1") (pinfunction "1_1") (pintype "passive"))
      (node (ref "L8") (pin "1") (pinfunction "1_1") (pintype "passive"))
      (node (ref "L9") (pin "2") (pinfunction "2_2") (pintype "passive"))
    )
    (net (code "48") (name "Net-(C65-Pad2)") (class "Default")
      (node (ref "C65") (pin "2") (pinfunction "2_2") (pintype "passive"))
      (node (ref "C66") (pin "2") (pinfunction "2_2") (pintype "passive"))
      (node (ref "C67") (pin "1") (pinfunction "1_1") (pintype "passive"))
      (node (ref "C72") (pin "1") (pinfunction "1_1") (pintype "passive"))
      (node (ref "L10") (pin "1") (pinfunction "1_1") (pintype "passive"))
      (node (ref "L11") (pin "2") (pinfunction "2_2") (pintype "passive"))
    )
    (net (code "49") (name "Net-(C67-Pad2)") (class "Default")
      (node (ref "C67") (pin "2") (pinfunction "2_2") (pintype "passive"))
      (node (ref "C68") (pin "2") (pinfunction "2_2") (pintype "passive"))
      (node (ref "C69") (pin "1") (pinfunction "1_1") (pintype "passive"))
      (node (ref "C73") (pin "1") (pinfunction "1_1") (pintype "passive"))
      (node (ref "L11") (pin "1") (pinfunction "1_1") (pintype "passive"))
      (node (ref "L12") (pin "2") (pinfunction "2_2") (pintype "passive"))
    )
    (net (code "50") (name "Net-(C92-Pad1)") (class "Default")
      (node (ref "C92") (pin "1") (pinfunction "1_1") (pintype "passive"))
      (node (ref "C93") (pin "1") (pinfunction "1_1") (pintype "passive"))
      (node (ref "C94") (pin "1") (pinfunction "1_1") (pintype "passive"))
      (node (ref "FB1") (pin "1") (pinfunction "1_1") (pintype "passive"))
      (node (ref "POWER") (pin "2") (pinfunction "2_2") (pintype "passive"))
      (node (ref "R61") (pin "1") (pinfunction "1_1") (pintype "passive"))
    )
    (net (code "51") (name "Net-(CLK_MODE-Pad2)") (class "Default")
      (node (ref "CLK_MODE") (pin "2") (pinfunction "2_2") (pintype "passive"))
      (node (ref "R2") (pin "2") (pinfunction "2_2") (pintype "passive"))
    )
    (net (code "52") (name "Net-(D1-A)") (class "Default")
      (node (ref "D1") (pin "1") (pinfunction "A_1") (pintype "passive"))
      (node (ref "R1") (pin "1") (pinfunction "1_1") (pintype "passive"))
    )
    (net (code "53") (name "Net-(D2-A)") (class "Default")
      (node (ref "D2") (pin "1") (pinfunction "A_1") (pintype "passive"))
      (node (ref "R10") (pin "1") (pinfunction "1_1") (pintype "passive"))
      (node (ref "U5") (pin "1") (pinfunction "PGOOD_1") (pintype "open_collector"))
    )
    (net (code "54") (name "Net-(D3-A)") (class "Default")
      (node (ref "D3") (pin "1") (pinfunction "A_1") (pintype "passive"))
      (node (ref "R61") (pin "2") (pinfunction "2_2") (pintype "passive"))
    )
    (net (code "55") (name "Net-(PMOD-Pad1)") (class "Default")
      (node (ref "PMOD") (pin "1") (pinfunction "1_1") (pintype "passive"))
      (node (ref "R17") (pin "1") (pinfunction "1_1") (pintype "passive"))
    )
    (net (code "56") (name "Net-(PMOD-Pad2)") (class "Default")
      (node (ref "PMOD") (pin "2") (pinfunction "2_2") (pintype "passive"))
      (node (ref "R18") (pin "2") (pinfunction "2_2") (pintype "passive"))
    )
    (net (code "57") (name "Net-(PMOD-Pad3)") (class "Default")
      (node (ref "PMOD") (pin "3") (pinfunction "3_3") (pintype "passive"))
      (node (ref "R19") (pin "1") (pinfunction "1_1") (pintype "passive"))
    )
    (net (code "58") (name "Net-(PMOD-Pad4)") (class "Default")
      (node (ref "PMOD") (pin "4") (pinfunction "4_4") (pintype "passive"))
      (node (ref "R20") (pin "2") (pinfunction "2_2") (pintype "passive"))
    )
    (net (code "59") (name "Net-(PMOD-Pad5)") (class "Default")
      (node (ref "PMOD") (pin "5") (pinfunction "5_5") (pintype "passive"))
      (node (ref "R21") (pin "1") (pinfunction "1_1") (pintype "passive"))
    )
    (net (code "60") (name "Net-(PMOD-Pad6)") (class "Default")
      (node (ref "PMOD") (pin "6") (pinfunction "6_6") (pintype "passive"))
      (node (ref "R22") (pin "2") (pinfunction "2_2") (pintype "passive"))
    )
    (net (code "61") (name "Net-(PMOD-Pad7)") (class "Default")
      (node (ref "PMOD") (pin "7") (pinfunction "7_7") (pintype "passive"))
      (node (ref "R23") (pin "1") (pinfunction "1_1") (pintype "passive"))
    )
    (net (code "62") (name "Net-(PMOD-Pad8)") (class "Default")
      (node (ref "PMOD") (pin "8") (pinfunction "8_8") (pintype "passive"))
      (node (ref "R24") (pin "2") (pinfunction "2_2") (pintype "passive"))
    )
    (net (code "63") (name "Net-(PMOD-Pad9)") (class "Default")
      (node (ref "PMOD") (pin "9") (pinfunction "9_9") (pintype "passive"))
      (node (ref "R25") (pin "1") (pinfunction "1_1") (pintype "passive"))
    )
    (net (code "64") (name "Net-(PMOD-Pad10)") (class "Default")
      (node (ref "PMOD") (pin "10") (pinfunction "10_10") (pintype "passive"))
      (node (ref "R26") (pin "2") (pinfunction "2_2") (pintype "passive"))
    )
    (net (code "65") (name "Net-(PMOD-Pad11)") (class "Default")
      (node (ref "PMOD") (pin "11") (pinfunction "11_11") (pintype "passive"))
      (node (ref "R27") (pin "1") (pinfunction "1_1") (pintype "passive"))
    )
    (net (code "66") (name "Net-(PMOD-Pad12)") (class "Default")
      (node (ref "PMOD") (pin "12") (pinfunction "12_12") (pintype "passive"))
      (node (ref "R28") (pin "2") (pinfunction "2_2") (pintype "passive"))
    )
    (net (code "67") (name "Net-(PMOD-Pad13)") (class "Default")
      (node (ref "PMOD") (pin "13") (pinfunction "13_13") (pintype "passive"))
      (node (ref "R29") (pin "1") (pinfunction "1_1") (pintype "passive"))
    )
    (net (code "68") (name "Net-(PMOD-Pad14)") (class "Default")
      (node (ref "PMOD") (pin "14") (pinfunction "14_14") (pintype "passive"))
      (node (ref "R30") (pin "2") (pinfunction "2_2") (pintype "passive"))
    )
    (net (code "69") (name "Net-(PMOD-Pad15)") (class "Default")
      (node (ref "PMOD") (pin "15") (pinfunction "15_15") (pintype "passive"))
      (node (ref "R31") (pin "1") (pinfunction "1_1") (pintype "passive"))
    )
    (net (code "70") (name "Net-(PMOD-Pad16)") (class "Default")
      (node (ref "PMOD") (pin "16") (pinfunction "16_16") (pintype "passive"))
      (node (ref "R32") (pin "2") (pinfunction "2_2") (pintype "passive"))
    )
    (net (code "71") (name "Net-(U1A-DAC_RSET)") (class "Default")
      (node (ref "R9") (pin "1") (pinfunction "1_1") (pintype "passive"))
      (node (ref "U1") (pin "17") (pinfunction "DAC_RSET_17") (pintype "input"))
    )
    (net (code "72") (name "Net-(U1A-LOOP_FILTER)") (class "Default")
      (node (ref "R8") (pin "1") (pinfunction "1_1") (pintype "passive"))
      (node (ref "U1") (pin "27") (pinfunction "LOOP_FILTER_27") (pintype "passive"))
    )
    (net (code "73") (name "Net-(U2-EN)") (class "Default")
      (node (ref "R3") (pin "1") (pinfunction "1_1") (pintype "passive"))
      (node (ref "U2") (pin "9") (pinfunction "EN_9") (pintype "passive"))
    )
    (net (code "74") (name "Net-(U2-FB{slash}NC)") (class "Default")
      (node (ref "R4") (pin "1") (pinfunction "1_1") (pintype "passive"))
      (node (ref "R5") (pin "2") (pinfunction "2_2") (pintype "passive"))
      (node (ref "U2") (pin "10") (pinfunction "FB/NC_10") (pintype "passive"))
    )
    (net (code "75") (name "Net-(U3-EN)") (class "Default")
      (node (ref "R6") (pin "1") (pinfunction "1_1") (pintype "passive"))
      (node (ref "U3") (pin "8") (pinfunction "EN_8") (pintype "passive"))
    )
    (net (code "76") (name "Net-(U4-EN)") (class "Default")
      (node (ref "R7") (pin "1") (pinfunction "1_1") (pintype "passive"))
      (node (ref "U4") (pin "8") (pinfunction "EN_8") (pintype "passive"))
    )
    (net (code "77") (name "Net-(U5-C1+)") (class "Default")
      (node (ref "C10") (pin "1") (pinfunction "1_1") (pintype "passive"))
      (node (ref "U5") (pin "10") (pinfunction "C1+_10") (pintype "passive"))
    )
    (net (code "78") (name "Net-(U5-C1-)") (class "Default")
      (node (ref "C10") (pin "2") (pinfunction "2_2") (pintype "passive"))
      (node (ref "U5") (pin "9") (pinfunction "C1-_9") (pintype "passive"))
    )
    (net (code "79") (name "Net-(U5-CP)") (class "Default")
      (node (ref "C11") (pin "1") (pinfunction "1_1") (pintype "passive"))
      (node (ref "U5") (pin "5") (pinfunction "CP_5") (pintype "passive"))
    )
    (net (code "80") (name "Net-(U5-EN+)") (class "Default")
      (node (ref "R12") (pin "2") (pinfunction "2_2") (pintype "passive"))
      (node (ref "U5") (pin "12") (pinfunction "EN+_12") (pintype "input"))
      (node (ref "U5") (pin "8") (pinfunction "EN-_8") (pintype "input"))
    )
    (net (code "81") (name "Net-(U5-FB+)") (class "Default")
      (node (ref "R13") (pin "2") (pinfunction "2_2") (pintype "passive"))
      (node (ref "R14") (pin "2") (pinfunction "2_2") (pintype "passive"))
      (node (ref "U5") (pin "2") (pinfunction "FB+_2") (pintype "input"))
    )
    (net (code "82") (name "Net-(U5-FB-)") (class "Default")
      (node (ref "R15") (pin "2") (pinfunction "2_2") (pintype "passive"))
      (node (ref "R16") (pin "1") (pinfunction "1_1") (pintype "passive"))
      (node (ref "U5") (pin "7") (pinfunction "FB-_7") (pintype "input"))
    )
    (net (code "83") (name "Net-(U6-IN+)") (class "Default")
      (node (ref "R34") (pin "2") (pinfunction "2_2") (pintype "passive"))
      (node (ref "R57") (pin "1") (pinfunction "1_1") (pintype "passive"))
      (node (ref "U6") (pin "3") (pinfunction "IN+_3") (pintype "input"))
    )
    (net (code "84") (name "Net-(U6-IN-)") (class "Default")
      (node (ref "R35") (pin "2") (pinfunction "2_2") (pintype "passive"))
      (node (ref "R37") (pin "1") (pinfunction "1_1") (pintype "passive"))
      (node (ref "U6") (pin "4") (pinfunction "IN-_4") (pintype "input"))
    )
    (net (code "85") (name "Net-(U6-OUT)") (class "Default")
      (node (ref "C28") (pin "2") (pinfunction "2_2") (pintype "passive"))
      (node (ref "C29") (pin "1") (pinfunction "1_1") (pintype "passive"))
      (node (ref "C35") (pin "1") (pinfunction "1_1") (pintype "passive"))
      (node (ref "L1") (pin "2") (pinfunction "2_2") (pintype "passive"))
      (node (ref "R37") (pin "2") (pinfunction "2_2") (pintype "passive"))
      (node (ref "U6") (pin "1") (pinfunction "OUT_1") (pintype "output"))
    )
    (net (code "86") (name "Net-(U7-IN+)") (class "Default")
      (node (ref "R39") (pin "2") (pinfunction "2_2") (pintype "passive"))
      (node (ref "R59") (pin "1") (pinfunction "1_1") (pintype "passive"))
      (node (ref "U7") (pin "3") (pinfunction "IN+_3") (pintype "input"))
    )
    (net (code "87") (name "Net-(U7-IN-)") (class "Default")
      (node (ref "R40") (pin "2") (pinfunction "2_2") (pintype "passive"))
      (node (ref "R42") (pin "1") (pinfunction "1_1") (pintype "passive"))
      (node (ref "U7") (pin "4") (pinfunction "IN-_4") (pintype "input"))
    )
    (net (code "88") (name "Net-(U7-OUT)") (class "Default")
      (node (ref "C40") (pin "2") (pinfunction "2_2") (pintype "passive"))
      (node (ref "C41") (pin "1") (pinfunction "1_1") (pintype "passive"))
      (node (ref "C47") (pin "1") (pinfunction "1_1") (pintype "passive"))
      (node (ref "L4") (pin "2") (pinfunction "2_2") (pintype "passive"))
      (node (ref "R42") (pin "2") (pinfunction "2_2") (pintype "passive"))
      (node (ref "U7") (pin "1") (pinfunction "OUT_1") (pintype "output"))
    )
    (net (code "89") (name "Net-(U8-IN+)") (class "Default")
      (node (ref "R44") (pin "2") (pinfunction "2_2") (pintype "passive"))
      (node (ref "R58") (pin "1") (pinfunction "1_1") (pintype "passive"))
      (node (ref "U8") (pin "3") (pinfunction "IN+_3") (pintype "input"))
    )
    (net (code "90") (name "Net-(U8-IN-)") (class "Default")
      (node (ref "R45") (pin "2") (pinfunction "2_2") (pintype "passive"))
      (node (ref "R47") (pin "1") (pinfunction "1_1") (pintype "passive"))
      (node (ref "U8") (pin "4") (pinfunction "IN-_4") (pintype "input"))
    )
    (net (code "91") (name "Net-(U8-OUT)") (class "Default")
      (node (ref "C52") (pin "2") (pinfunction "2_2") (pintype "passive"))
      (node (ref "C53") (pin "1") (pinfunction "1_1") (pintype "passive"))
      (node (ref "C59") (pin "1") (pinfunction "1_1") (pintype "passive"))
      (node (ref "L7") (pin "2") (pinfunction "2_2") (pintype "passive"))
      (node (ref "R47") (pin "2") (pinfunction "2_2") (pintype "passive"))
      (node (ref "U8") (pin "1") (pinfunction "OUT_1") (pintype "output"))
    )
    (net (code "92") (name "Net-(U9-IN+)") (class "Default")
      (node (ref "R49") (pin "2") (pinfunction "2_2") (pintype "passive"))
      (node (ref "R60") (pin "1") (pinfunction "1_1") (pintype "passive"))
      (node (ref "U9") (pin "3") (pinfunction "IN+_3") (pintype "input"))
    )
    (net (code "93") (name "Net-(U9-IN-)") (class "Default")
      (node (ref "R50") (pin "2") (pinfunction "2_2") (pintype "passive"))
      (node (ref "R52") (pin "1") (pinfunction "1_1") (pintype "passive"))
      (node (ref "U9") (pin "4") (pinfunction "IN-_4") (pintype "input"))
    )
    (net (code "94") (name "Net-(U9-OUT)") (class "Default")
      (node (ref "C64") (pin "2") (pinfunction "2_2") (pintype "passive"))
      (node (ref "C65") (pin "1") (pinfunction "1_1") (pintype "passive"))
      (node (ref "C71") (pin "1") (pinfunction "1_1") (pintype "passive"))
      (node (ref "L10") (pin "2") (pinfunction "2_2") (pintype "passive"))
      (node (ref "R52") (pin "2") (pinfunction "2_2") (pintype "passive"))
      (node (ref "U9") (pin "1") (pinfunction "OUT_1") (pintype "output"))
    )
    (net (code "95") (name "Net-(U10-+IN)") (class "Default")
      (node (ref "C33") (pin "2") (pinfunction "2_2") (pintype "passive"))
      (node (ref "C34") (pin "1") (pinfunction "1_1") (pintype "passive"))
      (node (ref "C38") (pin "2") (pinfunction "2_2") (pintype "passive"))
      (node (ref "L3") (pin "1") (pinfunction "1_1") (pintype "passive"))
      (node (ref "U10") (pin "3") (pinfunction "+IN_3") (pintype "input"))
    )
    (net (code "96") (name "Net-(U10-OUT)") (class "Default")
      (node (ref "C131") (pin "1") (pinfunction "1_1") (pintype "passive"))
      (node (ref "R53") (pin "1") (pinfunction "1_1") (pintype "passive"))
      (node (ref "U10") (pin "1") (pinfunction "OUT_1") (pintype "output"))
    )
    (net (code "97") (name "Net-(U11-+IN)") (class "Default")
      (node (ref "C45") (pin "2") (pinfunction "2_2") (pintype "passive"))
      (node (ref "C46") (pin "1") (pinfunction "1_1") (pintype "passive"))
      (node (ref "C50") (pin "2") (pinfunction "2_2") (pintype "passive"))
      (node (ref "L6") (pin "1") (pinfunction "1_1") (pintype "passive"))
      (node (ref "U11") (pin "3") (pinfunction "+IN_3") (pintype "input"))
    )
    (net (code "98") (name "Net-(U11-OUT)") (class "Default")
      (node (ref "C132") (pin "1") (pinfunction "1_1") (pintype "passive"))
      (node (ref "R54") (pin "1") (pinfunction "1_1") (pintype "passive"))
      (node (ref "U11") (pin "1") (pinfunction "OUT_1") (pintype "output"))
    )
    (net (code "99") (name "Net-(U12-+IN)") (class "Default")
      (node (ref "C57") (pin "2") (pinfunction "2_2") (pintype "passive"))
      (node (ref "C58") (pin "1") (pinfunction "1_1") (pintype "passive"))
      (node (ref "C62") (pin "2") (pinfunction "2_2") (pintype "passive"))
      (node (ref "L9") (pin "1") (pinfunction "1_1") (pintype "passive"))
      (node (ref "U12") (pin "3") (pinfunction "+IN_3") (pintype "input"))
    )
    (net (code "100") (name "Net-(U12-OUT)") (class "Default")
      (node (ref "C133") (pin "1") (pinfunction "1_1") (pintype "passive"))
      (node (ref "R55") (pin "1") (pinfunction "1_1") (pintype "passive"))
      (node (ref "U12") (pin "1") (pinfunction "OUT_1") (pintype "output"))
    )
    (net (code "101") (name "Net-(U13-+IN)") (class "Default")
      (node (ref "C69") (pin "2") (pinfunction "2_2") (pintype "passive"))
      (node (ref "C70") (pin "1") (pinfunction "1_1") (pintype "passive"))
      (node (ref "C74") (pin "2") (pinfunction "2_2") (pintype "passive"))
      (node (ref "L12") (pin "1") (pinfunction "1_1") (pintype "passive"))
      (node (ref "U13") (pin "3") (pinfunction "+IN_3") (pintype "input"))
    )
    (net (code "102") (name "Net-(U13-OUT)") (class "Default")
      (node (ref "C134") (pin "1") (pinfunction "1_1") (pintype "passive"))
      (node (ref "R56") (pin "1") (pinfunction "1_1") (pintype "passive"))
      (node (ref "U13") (pin "1") (pinfunction "OUT_1") (pintype "output"))
    )
    (net (code "103") (name "unconnected-(U2-NC_1-Pad3)") (class "Default")
      (node (ref "U2") (pin "3") (pinfunction "NC_1_3") (pintype "passive+no_connect"))
    )
    (net (code "104") (name "unconnected-(U2-NC_2-Pad4)") (class "Default")
      (node (ref "U2") (pin "4") (pinfunction "NC_2_4") (pintype "passive+no_connect"))
    )
    (net (code "105") (name "unconnected-(U2-NC_3-Pad13)") (class "Default")
      (node (ref "U2") (pin "13") (pinfunction "NC_3_13") (pintype "passive+no_connect"))
    )
  )
)
